# sch-knx-valve-control_v1_0.net
KiCad netlist of a schematic drawn in EasyEDA
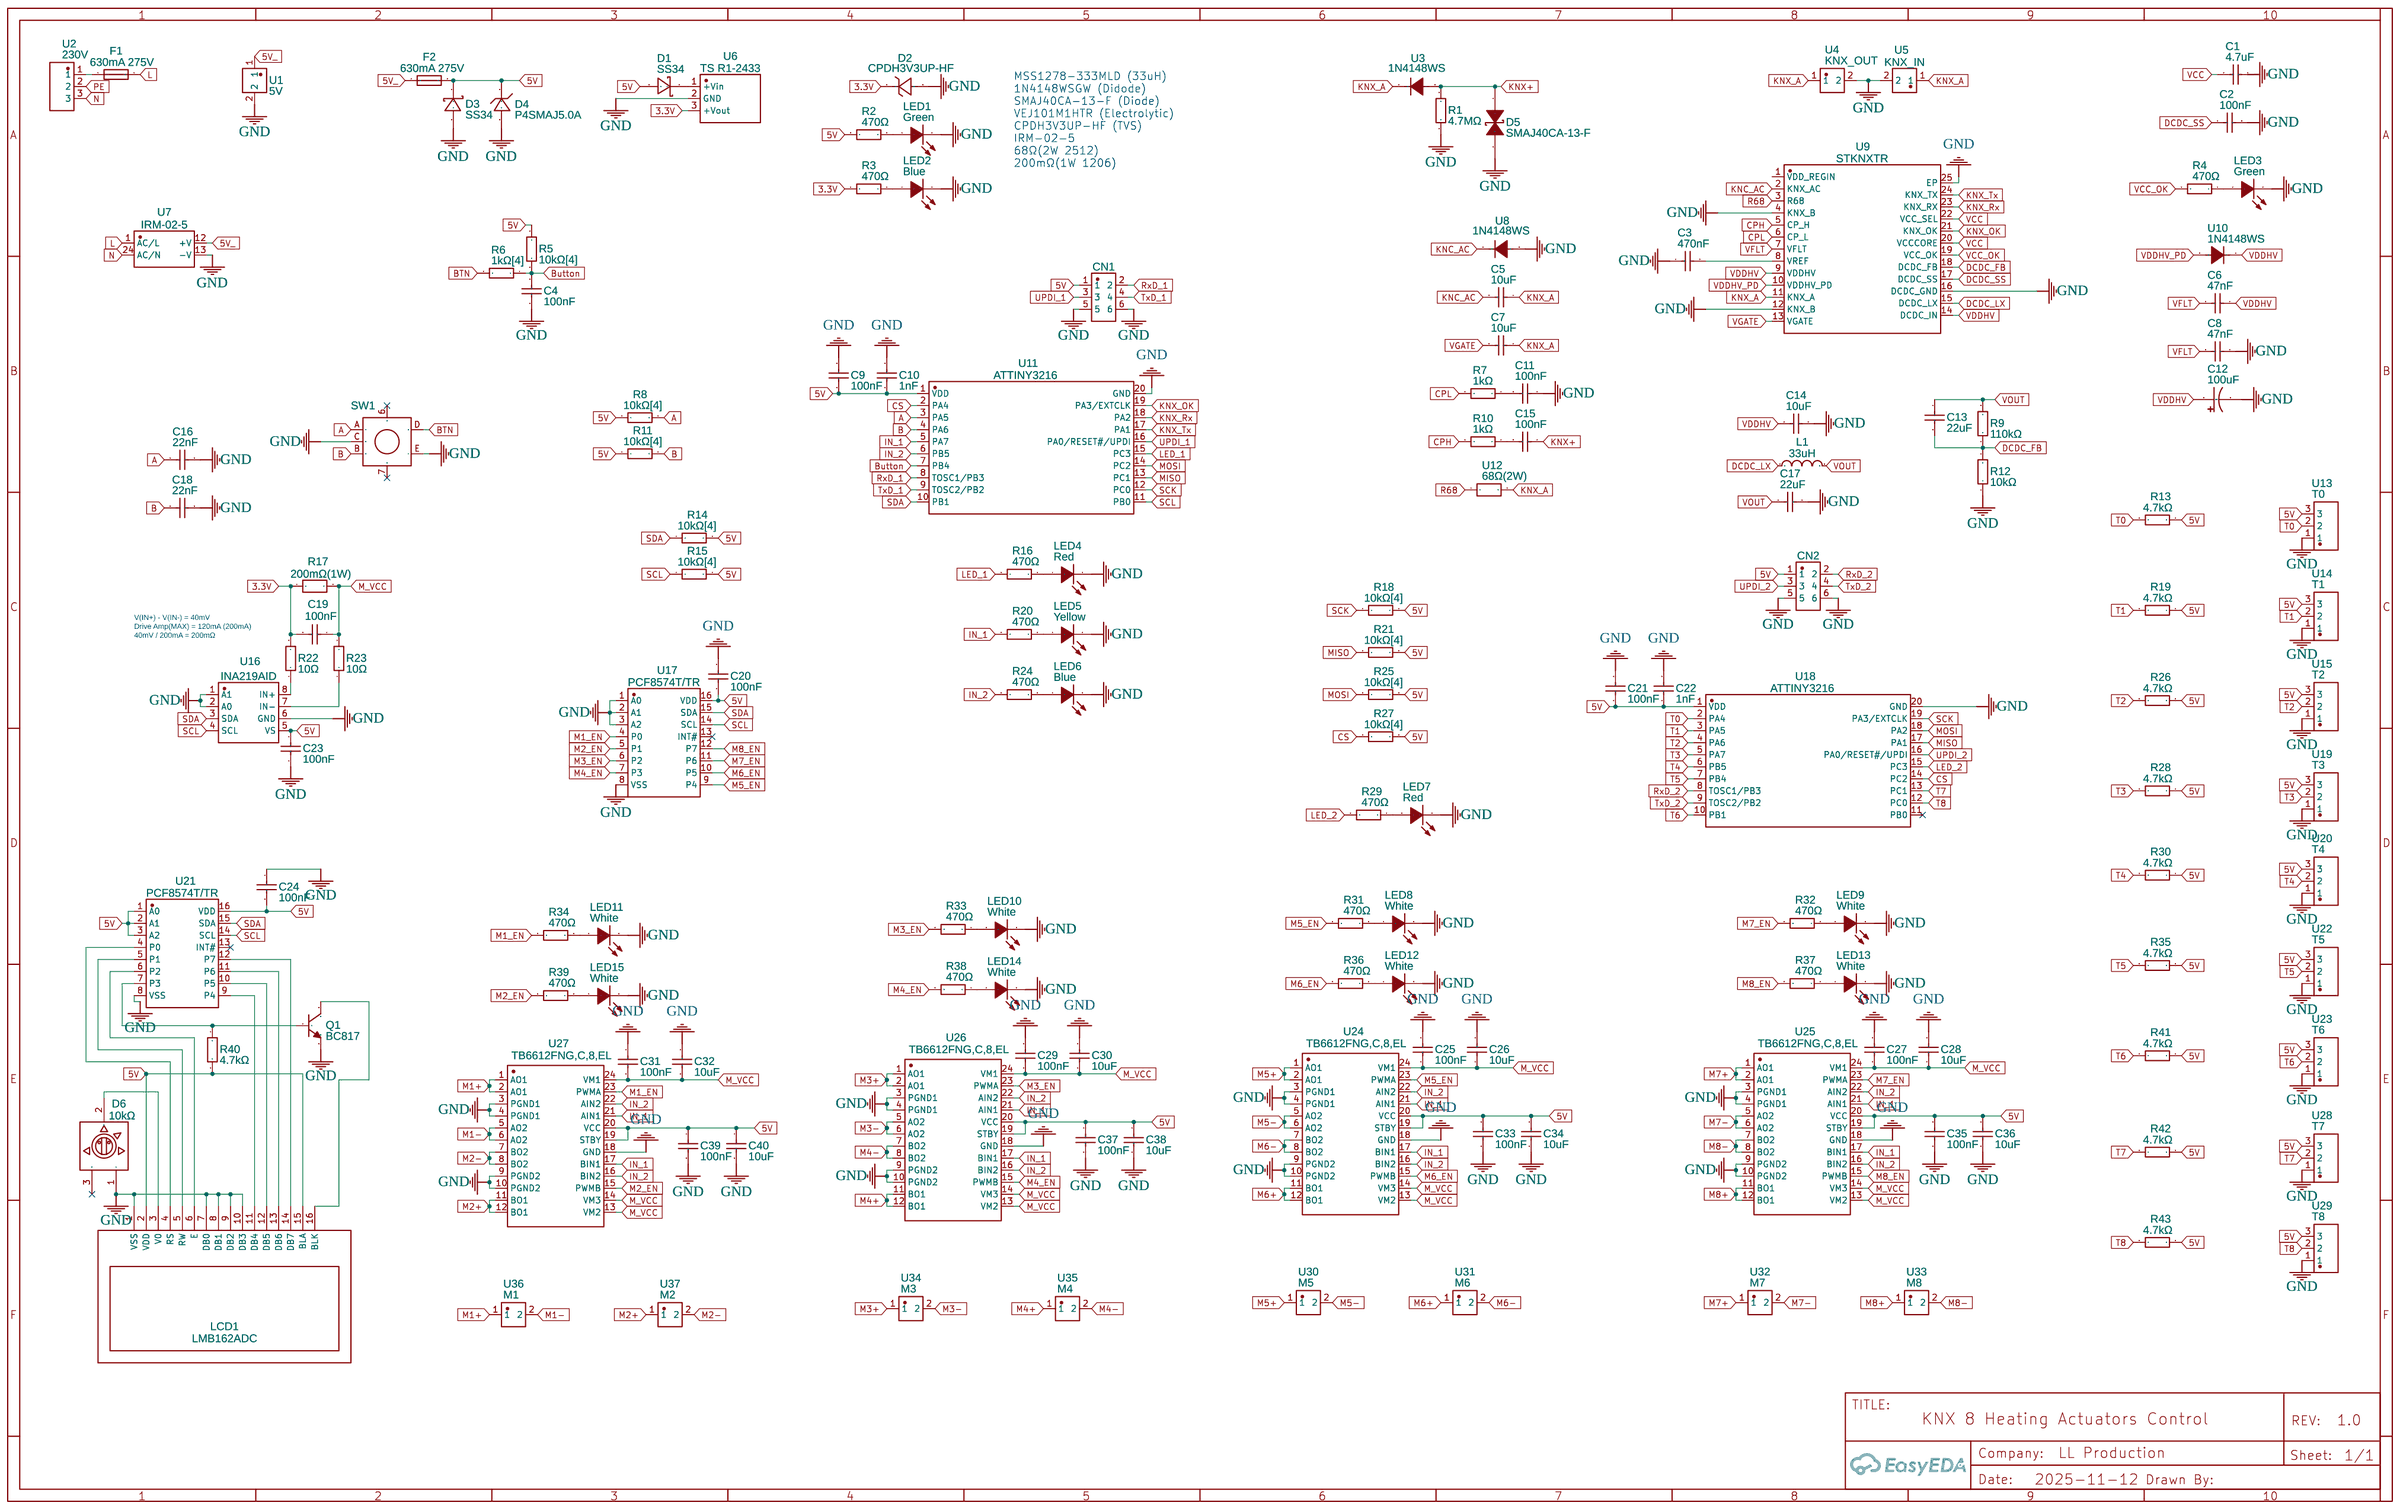
[diagram p0: schematic sheet]

(export (version "E")
  (design (tool "Eeschema 10.0.6"))
  (components
    (comp (ref "C1")
      (value "4.7uF")
      (fields (field (name "Manufacturer Part") "CC0603KRX7R9BB103") (field (name "Manufacturer") "YAGEO"))
      (libsource (lib "") (part "CC0603KRX7R9BB103_2"))
    )
    (comp (ref "C2")
      (value "100nF")
      (fields (field (name "Manufacturer Part") "CC0603KRX7R9BB103") (field (name "Manufacturer") "YAGEO"))
      (libsource (lib "") (part "CC0603KRX7R9BB103"))
    )
    (comp (ref "C3")
      (value "470nF")
      (fields (field (name "Manufacturer Part") "CC0603KRX7R9BB103") (field (name "Manufacturer") "YAGEO"))
      (libsource (lib "") (part "CC0603KRX7R9BB103"))
    )
    (comp (ref "C4")
      (value "100nF")
      (fields (field (name "Manufacturer Part") "CC0603KRX7R9BB103") (field (name "Manufacturer") "YAGEO"))
      (libsource (lib "") (part "CC0603KRX7R9BB103_1"))
    )
    (comp (ref "C5")
      (value "10uF")
      (fields (field (name "Manufacturer Part") "CC0603KRX7R9BB103") (field (name "Manufacturer") "YAGEO"))
      (libsource (lib "") (part "CC0603KRX7R9BB103_2"))
    )
    (comp (ref "C6")
      (value "47nF")
      (fields (field (name "Manufacturer Part") "CC0603KRX7R9BB103") (field (name "Manufacturer") "YAGEO"))
      (libsource (lib "") (part "CC0603KRX7R9BB103_2"))
    )
    (comp (ref "C7")
      (value "10uF")
      (fields (field (name "Manufacturer Part") "CC0603KRX7R9BB103") (field (name "Manufacturer") "YAGEO"))
      (libsource (lib "") (part "CC0603KRX7R9BB103_2"))
    )
    (comp (ref "C8")
      (value "47nF")
      (fields (field (name "Manufacturer Part") "CC0603KRX7R9BB103") (field (name "Manufacturer") "YAGEO"))
      (libsource (lib "") (part "CC0603KRX7R9BB103_2"))
    )
    (comp (ref "C9")
      (value "100nF")
      (fields (field (name "Manufacturer Part") "CC0603KRX7R9BB103") (field (name "Manufacturer") "YAGEO"))
      (libsource (lib "") (part "CC0603KRX7R9BB103_3"))
    )
    (comp (ref "C10")
      (value "1nF")
      (fields (field (name "Manufacturer Part") "CC0603KRX7R9BB103") (field (name "Manufacturer") "YAGEO"))
      (libsource (lib "") (part "CC0603KRX7R9BB103_3"))
    )
    (comp (ref "C11")
      (value "100nF")
      (fields (field (name "Manufacturer Part") "CC0603KRX7R9BB103") (field (name "Manufacturer") "YAGEO"))
      (libsource (lib "") (part "CC0603KRX7R9BB103_2"))
    )
    (comp (ref "C12")
      (value "100uF")
      (fields (field (name "Manufacturer Part") "VEJ101M1HTR-0810") (field (name "Manufacturer") "Lelon(立隆)"))
      (libsource (lib "") (part "VEJ101M1HTR-0810"))
    )
    (comp (ref "C13")
      (value "22uF")
      (fields (field (name "Manufacturer Part") "CC0603KRX7R9BB103") (field (name "Manufacturer") "YAGEO"))
      (libsource (lib "") (part "CC0603KRX7R9BB103_1"))
    )
    (comp (ref "C14")
      (value "10uF")
      (fields (field (name "Manufacturer Part") "CC0603KRX7R9BB103") (field (name "Manufacturer") "YAGEO"))
      (libsource (lib "") (part "CC0603KRX7R9BB103"))
    )
    (comp (ref "C15")
      (value "100nF")
      (fields (field (name "Manufacturer Part") "CC0603KRX7R9BB103") (field (name "Manufacturer") "YAGEO"))
      (libsource (lib "") (part "CC0603KRX7R9BB103_2"))
    )
    (comp (ref "C16")
      (value "22nF")
      (fields (field (name "Manufacturer Part") "CC0603KRX7R9BB103") (field (name "Manufacturer") "YAGEO"))
      (libsource (lib "") (part "CC0603KRX7R9BB103_2"))
    )
    (comp (ref "C17")
      (value "22uF")
      (fields (field (name "Manufacturer Part") "CC0603KRX7R9BB103") (field (name "Manufacturer") "YAGEO"))
      (libsource (lib "") (part "CC0603KRX7R9BB103"))
    )
    (comp (ref "C18")
      (value "22nF")
      (fields (field (name "Manufacturer Part") "CC0603KRX7R9BB103") (field (name "Manufacturer") "YAGEO"))
      (libsource (lib "") (part "CC0603KRX7R9BB103_2"))
    )
    (comp (ref "C19")
      (value "100nF")
      (fields (field (name "Manufacturer Part") "CC0603KRX7R9BB103") (field (name "Manufacturer") "YAGEO"))
      (libsource (lib "") (part "CC0603KRX7R9BB103_2"))
    )
    (comp (ref "C20")
      (value "100nF")
      (fields (field (name "Manufacturer Part") "CC0603KRX7R9BB103") (field (name "Manufacturer") "YAGEO"))
      (libsource (lib "") (part "CC0603KRX7R9BB103_1"))
    )
    (comp (ref "C21")
      (value "100nF")
      (fields (field (name "Manufacturer Part") "CC0603KRX7R9BB103") (field (name "Manufacturer") "YAGEO"))
      (libsource (lib "") (part "CC0603KRX7R9BB103_3"))
    )
    (comp (ref "C22")
      (value "1nF")
      (fields (field (name "Manufacturer Part") "CC0603KRX7R9BB103") (field (name "Manufacturer") "YAGEO"))
      (libsource (lib "") (part "CC0603KRX7R9BB103_3"))
    )
    (comp (ref "C23")
      (value "100nF")
      (fields (field (name "Manufacturer Part") "CC0603KRX7R9BB103") (field (name "Manufacturer") "YAGEO"))
      (libsource (lib "") (part "CC0603KRX7R9BB103_1"))
    )
    (comp (ref "C24")
      (value "100nF")
      (fields (field (name "Manufacturer Part") "CC0603KRX7R9BB103") (field (name "Manufacturer") "YAGEO"))
      (libsource (lib "") (part "CC0603KRX7R9BB103_1"))
    )
    (comp (ref "C25")
      (value "100nF")
      (fields (field (name "Manufacturer Part") "CC0603KRX7R9BB103") (field (name "Manufacturer") "YAGEO"))
      (libsource (lib "") (part "CC0603KRX7R9BB103_1"))
    )
    (comp (ref "C26")
      (value "10uF")
      (fields (field (name "Manufacturer Part") "CC0603KRX7R9BB103") (field (name "Manufacturer") "YAGEO"))
      (libsource (lib "") (part "CC0603KRX7R9BB103_1"))
    )
    (comp (ref "C27")
      (value "100nF")
      (fields (field (name "Manufacturer Part") "CC0603KRX7R9BB103") (field (name "Manufacturer") "YAGEO"))
      (libsource (lib "") (part "CC0603KRX7R9BB103_1"))
    )
    (comp (ref "C28")
      (value "10uF")
      (fields (field (name "Manufacturer Part") "CC0603KRX7R9BB103") (field (name "Manufacturer") "YAGEO"))
      (libsource (lib "") (part "CC0603KRX7R9BB103_1"))
    )
    (comp (ref "C29")
      (value "100nF")
      (fields (field (name "Manufacturer Part") "CC0603KRX7R9BB103") (field (name "Manufacturer") "YAGEO"))
      (libsource (lib "") (part "CC0603KRX7R9BB103_1"))
    )
    (comp (ref "C30")
      (value "10uF")
      (fields (field (name "Manufacturer Part") "CC0603KRX7R9BB103") (field (name "Manufacturer") "YAGEO"))
      (libsource (lib "") (part "CC0603KRX7R9BB103_1"))
    )
    (comp (ref "C31")
      (value "100nF")
      (fields (field (name "Manufacturer Part") "CC0603KRX7R9BB103") (field (name "Manufacturer") "YAGEO"))
      (libsource (lib "") (part "CC0603KRX7R9BB103_1"))
    )
    (comp (ref "C32")
      (value "10uF")
      (fields (field (name "Manufacturer Part") "CC0603KRX7R9BB103") (field (name "Manufacturer") "YAGEO"))
      (libsource (lib "") (part "CC0603KRX7R9BB103_1"))
    )
    (comp (ref "C33")
      (value "100nF")
      (fields (field (name "Manufacturer Part") "CC0603KRX7R9BB103") (field (name "Manufacturer") "YAGEO"))
      (libsource (lib "") (part "CC0603KRX7R9BB103_1"))
    )
    (comp (ref "C34")
      (value "10uF")
      (fields (field (name "Manufacturer Part") "CC0603KRX7R9BB103") (field (name "Manufacturer") "YAGEO"))
      (libsource (lib "") (part "CC0603KRX7R9BB103_1"))
    )
    (comp (ref "C35")
      (value "100nF")
      (fields (field (name "Manufacturer Part") "CC0603KRX7R9BB103") (field (name "Manufacturer") "YAGEO"))
      (libsource (lib "") (part "CC0603KRX7R9BB103_1"))
    )
    (comp (ref "C36")
      (value "10uF")
      (fields (field (name "Manufacturer Part") "CC0603KRX7R9BB103") (field (name "Manufacturer") "YAGEO"))
      (libsource (lib "") (part "CC0603KRX7R9BB103_1"))
    )
    (comp (ref "C37")
      (value "100nF")
      (fields (field (name "Manufacturer Part") "CC0603KRX7R9BB103") (field (name "Manufacturer") "YAGEO"))
      (libsource (lib "") (part "CC0603KRX7R9BB103_1"))
    )
    (comp (ref "C38")
      (value "10uF")
      (fields (field (name "Manufacturer Part") "CC0603KRX7R9BB103") (field (name "Manufacturer") "YAGEO"))
      (libsource (lib "") (part "CC0603KRX7R9BB103_1"))
    )
    (comp (ref "C39")
      (value "100nF")
      (fields (field (name "Manufacturer Part") "CC0603KRX7R9BB103") (field (name "Manufacturer") "YAGEO"))
      (libsource (lib "") (part "CC0603KRX7R9BB103_1"))
    )
    (comp (ref "C40")
      (value "10uF")
      (fields (field (name "Manufacturer Part") "CC0603KRX7R9BB103") (field (name "Manufacturer") "YAGEO"))
      (libsource (lib "") (part "CC0603KRX7R9BB103_1"))
    )
    (comp (ref "CN1")
      (value "321006SG0ABK00A01")
      (fields (field (name "Manufacturer") "JILN(锦凌)"))
      (libsource (lib "") (part "321006SG0ABK00A01"))
    )
    (comp (ref "CN2")
      (value "321006SG0ABK00A01")
      (fields (field (name "Manufacturer") "JILN(锦凌)"))
      (libsource (lib "") (part "321006SG0ABK00A01"))
    )
    (comp (ref "D1")
      (value "SS34")
      (fields (field (name "Manufacturer") "MDD"))
      (libsource (lib "") (part "SS34_C8678_1"))
    )
    (comp (ref "D2")
      (value "CPDH3V3UP-HF")
      (fields (field (name "Manufacturer Part") "SOD-523"))
      (libsource (lib "") (part "SOD-523"))
    )
    (comp (ref "D3")
      (value "SS34")
      (fields (field (name "Manufacturer") "MDD"))
      (libsource (lib "") (part "SS34_C8678"))
    )
    (comp (ref "D4")
      (value "P4SMAJ5.0A")
      (fields
        (field (name "Manufacturer Part") "P4SMAJ12A_R1_00001")
        (field (name "Manufacturer") "PANJIT(强茂)")
      )
      (libsource (lib "") (part "P4SMAJ12A-PEC"))
    )
    (comp (ref "D5")
      (value "SMAJ40CA-13-F")
      (fields (field (name "Manufacturer") "DIODES(美台)"))
      (libsource (lib "") (part "SMAJ40CA-13-F"))
    )
    (comp (ref "D6")
      (value "10kΩ")
      (fields (field (name "Manufacturer Part") "3314G-1-103E") (field (name "Manufacturer") "BOURNS"))
      (libsource (lib "") (part "3314G-1-103E"))
    )
    (comp (ref "F1")
      (value "630mA 275V")
      (fields (field (name "Manufacturer Part") "S1032-F-60.0A") (field (name "Manufacturer") "SART(萨特)"))
      (libsource (lib "") (part "S1032-F-60.0A"))
    )
    (comp (ref "F2")
      (value "630mA 275V")
      (fields (field (name "Manufacturer Part") "S1032-F-60.0A") (field (name "Manufacturer") "SART(萨特)"))
      (libsource (lib "") (part "S1032-F-60.0A"))
    )
    (comp (ref "L1")
      (value "33uH")
      (fields (field (name "Manufacturer Part") "MSS1278-333MLD"))
      (libsource (lib "") (part "MSS1278-333MLD"))
    )
    (comp (ref "LCD1")
      (value "LMB162ADC")
      (fields (field (name "Manufacturer") "TOPWAY"))
      (libsource (lib "") (part "LMB162ADC"))
    )
    (comp (ref "LED1")
      (value "Green")
      (fields (field (name "Manufacturer Part") "SZYY0603R") (field (name "Manufacturer") "yongyu(永裕光电)"))
      (libsource (lib "") (part "SZYY0603R"))
    )
    (comp (ref "LED2")
      (value "Blue")
      (fields (field (name "Manufacturer Part") "SZYY0603R") (field (name "Manufacturer") "yongyu(永裕光电)"))
      (libsource (lib "") (part "SZYY0603R"))
    )
    (comp (ref "LED3")
      (value "Green")
      (fields (field (name "Manufacturer Part") "SZYY0603R") (field (name "Manufacturer") "yongyu(永裕光电)"))
      (libsource (lib "") (part "SZYY0603R"))
    )
    (comp (ref "LED4")
      (value "Red")
      (fields (field (name "Manufacturer Part") "SZYY0603R") (field (name "Manufacturer") "yongyu(永裕光电)"))
      (libsource (lib "") (part "SZYY0603R"))
    )
    (comp (ref "LED5")
      (value "Yellow")
      (fields (field (name "Manufacturer Part") "SZYY0603R") (field (name "Manufacturer") "yongyu(永裕光电)"))
      (libsource (lib "") (part "SZYY0603R"))
    )
    (comp (ref "LED6")
      (value "Blue")
      (fields (field (name "Manufacturer Part") "SZYY0603R") (field (name "Manufacturer") "yongyu(永裕光电)"))
      (libsource (lib "") (part "SZYY0603R"))
    )
    (comp (ref "LED7")
      (value "Red")
      (fields (field (name "Manufacturer Part") "SZYY0603R") (field (name "Manufacturer") "yongyu(永裕光电)"))
      (libsource (lib "") (part "SZYY0603R"))
    )
    (comp (ref "LED8")
      (value "White")
      (fields (field (name "Manufacturer Part") "SZYY0603R") (field (name "Manufacturer") "yongyu(永裕光电)"))
      (libsource (lib "") (part "SZYY0603R"))
    )
    (comp (ref "LED9")
      (value "White")
      (fields (field (name "Manufacturer Part") "SZYY0603R") (field (name "Manufacturer") "yongyu(永裕光电)"))
      (libsource (lib "") (part "SZYY0603R"))
    )
    (comp (ref "LED10")
      (value "White")
      (fields (field (name "Manufacturer Part") "SZYY0603R") (field (name "Manufacturer") "yongyu(永裕光电)"))
      (libsource (lib "") (part "SZYY0603R"))
    )
    (comp (ref "LED11")
      (value "White")
      (fields (field (name "Manufacturer Part") "SZYY0603R") (field (name "Manufacturer") "yongyu(永裕光电)"))
      (libsource (lib "") (part "SZYY0603R"))
    )
    (comp (ref "LED12")
      (value "White")
      (fields (field (name "Manufacturer Part") "SZYY0603R") (field (name "Manufacturer") "yongyu(永裕光电)"))
      (libsource (lib "") (part "SZYY0603R"))
    )
    (comp (ref "LED13")
      (value "White")
      (fields (field (name "Manufacturer Part") "SZYY0603R") (field (name "Manufacturer") "yongyu(永裕光电)"))
      (libsource (lib "") (part "SZYY0603R"))
    )
    (comp (ref "LED14")
      (value "White")
      (fields (field (name "Manufacturer Part") "SZYY0603R") (field (name "Manufacturer") "yongyu(永裕光电)"))
      (libsource (lib "") (part "SZYY0603R"))
    )
    (comp (ref "LED15")
      (value "White")
      (fields (field (name "Manufacturer Part") "SZYY0603R") (field (name "Manufacturer") "yongyu(永裕光电)"))
      (libsource (lib "") (part "SZYY0603R"))
    )
    (comp (ref "Q1")
      (value "BC817")
      (fields (field (name "Manufacturer Part") "BC817-40,215") (field (name "Manufacturer") "Nexperia(安世)"))
      (libsource (lib "") (part "BC817-40,215"))
    )
    (comp (ref "R1")
      (value "4.7MΩ")
      (fields (field (name "Manufacturer Part") "CR0603FA1001G") (field (name "Manufacturer") "LIZ(丽智电子)"))
      (libsource (lib "") (part "CR0603FA1001G_C126900_1"))
    )
    (comp (ref "R2")
      (value "470Ω")
      (fields (field (name "Manufacturer Part") "CR0603FA1001G") (field (name "Manufacturer") "LIZ(丽智电子)"))
      (libsource (lib "") (part "CR0603FA1001G_C126900"))
    )
    (comp (ref "R3")
      (value "470Ω")
      (fields (field (name "Manufacturer Part") "CR0603FA1001G") (field (name "Manufacturer") "LIZ(丽智电子)"))
      (libsource (lib "") (part "CR0603FA1001G_C126900"))
    )
    (comp (ref "R4")
      (value "470Ω")
      (fields (field (name "Manufacturer Part") "CR0603FA1001G") (field (name "Manufacturer") "LIZ(丽智电子)"))
      (libsource (lib "") (part "CR0603FA1001G_C126900"))
    )
    (comp (ref "R5")
      (value "10kΩ[4]")
      (fields
        (field (name "Manufacturer Part") "0402WGF1002TCE")
        (field (name "Manufacturer") "UNI-ROYAL(厚声)")
      )
      (libsource (lib "") (part "0402WGF1002TCE_2"))
    )
    (comp (ref "R6")
      (value "1kΩ[4]")
      (fields
        (field (name "Manufacturer Part") "0402WGF1002TCE")
        (field (name "Manufacturer") "UNI-ROYAL(厚声)")
      )
      (libsource (lib "") (part "0402WGF1002TCE"))
    )
    (comp (ref "R7")
      (value "1kΩ")
      (fields (field (name "Manufacturer Part") "CR0603FA1001G") (field (name "Manufacturer") "LIZ(丽智电子)"))
      (libsource (lib "") (part "CR0603FA1001G_C126900"))
    )
    (comp (ref "R8")
      (value "10kΩ[4]")
      (fields
        (field (name "Manufacturer Part") "0402WGF1002TCE")
        (field (name "Manufacturer") "UNI-ROYAL(厚声)")
      )
      (libsource (lib "") (part "0402WGF1002TCE_1"))
    )
    (comp (ref "R9")
      (value "110kΩ")
      (fields (field (name "Manufacturer Part") "CR0603FA1001G") (field (name "Manufacturer") "LIZ(丽智电子)"))
      (libsource (lib "") (part "CR0603FA1001G_C126900_1"))
    )
    (comp (ref "R10")
      (value "1kΩ")
      (fields (field (name "Manufacturer Part") "CR0603FA1001G") (field (name "Manufacturer") "LIZ(丽智电子)"))
      (libsource (lib "") (part "CR0603FA1001G_C126900"))
    )
    (comp (ref "R11")
      (value "10kΩ[4]")
      (fields
        (field (name "Manufacturer Part") "0402WGF1002TCE")
        (field (name "Manufacturer") "UNI-ROYAL(厚声)")
      )
      (libsource (lib "") (part "0402WGF1002TCE_1"))
    )
    (comp (ref "R12")
      (value "10kΩ")
      (fields (field (name "Manufacturer Part") "CR0603FA1001G") (field (name "Manufacturer") "LIZ(丽智电子)"))
      (libsource (lib "") (part "CR0603FA1001G_C126900_1"))
    )
    (comp (ref "R13")
      (value "4.7kΩ")
      (fields (field (name "Manufacturer Part") "CR0603FA1001G") (field (name "Manufacturer") "LIZ(丽智电子)"))
      (libsource (lib "") (part "CR0603FA1001G_C126900"))
    )
    (comp (ref "R14")
      (value "10kΩ[4]")
      (fields
        (field (name "Manufacturer Part") "0402WGF1002TCE")
        (field (name "Manufacturer") "UNI-ROYAL(厚声)")
      )
      (libsource (lib "") (part "0402WGF1002TCE_1"))
    )
    (comp (ref "R15")
      (value "10kΩ[4]")
      (fields
        (field (name "Manufacturer Part") "0402WGF1002TCE")
        (field (name "Manufacturer") "UNI-ROYAL(厚声)")
      )
      (libsource (lib "") (part "0402WGF1002TCE_1"))
    )
    (comp (ref "R16")
      (value "470Ω")
      (fields (field (name "Manufacturer Part") "CR0603FA1001G") (field (name "Manufacturer") "LIZ(丽智电子)"))
      (libsource (lib "") (part "CR0603FA1001G_C126900"))
    )
    (comp (ref "R17")
      (value "200mΩ(1W)")
      (fields (field (name "Manufacturer Part") "SCR1206F1M1") (field (name "Manufacturer") "VO(翔胜)"))
      (libsource (lib "") (part "SCR1206F1M1"))
    )
    (comp (ref "R18")
      (value "10kΩ[4]")
      (fields
        (field (name "Manufacturer Part") "0402WGF1002TCE")
        (field (name "Manufacturer") "UNI-ROYAL(厚声)")
      )
      (libsource (lib "") (part "0402WGF1002TCE_1"))
    )
    (comp (ref "R19")
      (value "4.7kΩ")
      (fields (field (name "Manufacturer Part") "CR0603FA1001G") (field (name "Manufacturer") "LIZ(丽智电子)"))
      (libsource (lib "") (part "CR0603FA1001G_C126900"))
    )
    (comp (ref "R20")
      (value "470Ω")
      (fields (field (name "Manufacturer Part") "CR0603FA1001G") (field (name "Manufacturer") "LIZ(丽智电子)"))
      (libsource (lib "") (part "CR0603FA1001G_C126900"))
    )
    (comp (ref "R21")
      (value "10kΩ[4]")
      (fields
        (field (name "Manufacturer Part") "0402WGF1002TCE")
        (field (name "Manufacturer") "UNI-ROYAL(厚声)")
      )
      (libsource (lib "") (part "0402WGF1002TCE_1"))
    )
    (comp (ref "R22")
      (value "10Ω")
      (fields (field (name "Manufacturer Part") "CR0603FA1001G") (field (name "Manufacturer") "LIZ(丽智电子)"))
      (libsource (lib "") (part "CR0603FA1001G_C126900_1"))
    )
    (comp (ref "R23")
      (value "10Ω")
      (fields (field (name "Manufacturer Part") "CR0603FA1001G") (field (name "Manufacturer") "LIZ(丽智电子)"))
      (libsource (lib "") (part "CR0603FA1001G_C126900_1"))
    )
    (comp (ref "R24")
      (value "470Ω")
      (fields (field (name "Manufacturer Part") "CR0603FA1001G") (field (name "Manufacturer") "LIZ(丽智电子)"))
      (libsource (lib "") (part "CR0603FA1001G_C126900"))
    )
    (comp (ref "R25")
      (value "10kΩ[4]")
      (fields
        (field (name "Manufacturer Part") "0402WGF1002TCE")
        (field (name "Manufacturer") "UNI-ROYAL(厚声)")
      )
      (libsource (lib "") (part "0402WGF1002TCE_1"))
    )
    (comp (ref "R26")
      (value "4.7kΩ")
      (fields (field (name "Manufacturer Part") "CR0603FA1001G") (field (name "Manufacturer") "LIZ(丽智电子)"))
      (libsource (lib "") (part "CR0603FA1001G_C126900"))
    )
    (comp (ref "R27")
      (value "10kΩ[4]")
      (fields
        (field (name "Manufacturer Part") "0402WGF1002TCE")
        (field (name "Manufacturer") "UNI-ROYAL(厚声)")
      )
      (libsource (lib "") (part "0402WGF1002TCE_1"))
    )
    (comp (ref "R28")
      (value "4.7kΩ")
      (fields (field (name "Manufacturer Part") "CR0603FA1001G") (field (name "Manufacturer") "LIZ(丽智电子)"))
      (libsource (lib "") (part "CR0603FA1001G_C126900"))
    )
    (comp (ref "R29")
      (value "470Ω")
      (fields (field (name "Manufacturer Part") "CR0603FA1001G") (field (name "Manufacturer") "LIZ(丽智电子)"))
      (libsource (lib "") (part "CR0603FA1001G_C126900"))
    )
    (comp (ref "R30")
      (value "4.7kΩ")
      (fields (field (name "Manufacturer Part") "CR0603FA1001G") (field (name "Manufacturer") "LIZ(丽智电子)"))
      (libsource (lib "") (part "CR0603FA1001G_C126900"))
    )
    (comp (ref "R31")
      (value "470Ω")
      (fields (field (name "Manufacturer Part") "CR0603FA1001G") (field (name "Manufacturer") "LIZ(丽智电子)"))
      (libsource (lib "") (part "CR0603FA1001G_C126900"))
    )
    (comp (ref "R32")
      (value "470Ω")
      (fields (field (name "Manufacturer Part") "CR0603FA1001G") (field (name "Manufacturer") "LIZ(丽智电子)"))
      (libsource (lib "") (part "CR0603FA1001G_C126900"))
    )
    (comp (ref "R33")
      (value "470Ω")
      (fields (field (name "Manufacturer Part") "CR0603FA1001G") (field (name "Manufacturer") "LIZ(丽智电子)"))
      (libsource (lib "") (part "CR0603FA1001G_C126900"))
    )
    (comp (ref "R34")
      (value "470Ω")
      (fields (field (name "Manufacturer Part") "CR0603FA1001G") (field (name "Manufacturer") "LIZ(丽智电子)"))
      (libsource (lib "") (part "CR0603FA1001G_C126900"))
    )
    (comp (ref "R35")
      (value "4.7kΩ")
      (fields (field (name "Manufacturer Part") "CR0603FA1001G") (field (name "Manufacturer") "LIZ(丽智电子)"))
      (libsource (lib "") (part "CR0603FA1001G_C126900"))
    )
    (comp (ref "R36")
      (value "470Ω")
      (fields (field (name "Manufacturer Part") "CR0603FA1001G") (field (name "Manufacturer") "LIZ(丽智电子)"))
      (libsource (lib "") (part "CR0603FA1001G_C126900"))
    )
    (comp (ref "R37")
      (value "470Ω")
      (fields (field (name "Manufacturer Part") "CR0603FA1001G") (field (name "Manufacturer") "LIZ(丽智电子)"))
      (libsource (lib "") (part "CR0603FA1001G_C126900"))
    )
    (comp (ref "R38")
      (value "470Ω")
      (fields (field (name "Manufacturer Part") "CR0603FA1001G") (field (name "Manufacturer") "LIZ(丽智电子)"))
      (libsource (lib "") (part "CR0603FA1001G_C126900"))
    )
    (comp (ref "R39")
      (value "470Ω")
      (fields (field (name "Manufacturer Part") "CR0603FA1001G") (field (name "Manufacturer") "LIZ(丽智电子)"))
      (libsource (lib "") (part "CR0603FA1001G_C126900"))
    )
    (comp (ref "R40")
      (value "4.7kΩ")
      (fields (field (name "Manufacturer Part") "CR0603FA1001G") (field (name "Manufacturer") "LIZ(丽智电子)"))
      (libsource (lib "") (part "CR0603FA1001G_C126900_2"))
    )
    (comp (ref "R41")
      (value "4.7kΩ")
      (fields (field (name "Manufacturer Part") "CR0603FA1001G") (field (name "Manufacturer") "LIZ(丽智电子)"))
      (libsource (lib "") (part "CR0603FA1001G_C126900"))
    )
    (comp (ref "R42")
      (value "4.7kΩ")
      (fields (field (name "Manufacturer Part") "CR0603FA1001G") (field (name "Manufacturer") "LIZ(丽智电子)"))
      (libsource (lib "") (part "CR0603FA1001G_C126900"))
    )
    (comp (ref "R43")
      (value "4.7kΩ")
      (fields (field (name "Manufacturer Part") "CR0603FA1001G") (field (name "Manufacturer") "LIZ(丽智电子)"))
      (libsource (lib "") (part "CR0603FA1001G_C126900"))
    )
    (comp (ref "SW1")
      (value "EC11L1525G01")
      (fields (field (name "Manufacturer") "ALPSALPINE(阿尔卑斯阿尔派)"))
      (libsource (lib "") (part "EC11L1525G01"))
    )
    (comp (ref "U1")
      (value "5V")
      (fields (field (name "Manufacturer Part") "2P,间距5.08mm,弹片压线升降式"))
      (libsource (lib "") (part "2P,间距5.08MM,弹片压线升降式_1"))
    )
    (comp (ref "U2")
      (value "230V")
      (fields
        (field (name "Manufacturer Part") "DB127V-5.08-3P-GN-S")
        (field (name "Manufacturer") "DIBO(地博电气)")
      )
      (libsource (lib "") (part "DB127V-5.08-3P-GN-S_1"))
    )
    (comp (ref "U3")
      (value "1N4148WS")
      (fields (field (name "Manufacturer") "Zhengxin(正芯)"))
      (libsource (lib "") (part "1N4148WS_1"))
    )
    (comp (ref "U4")
      (value "KNX_OUT")
      (fields (field (name "Manufacturer Part") "2P,间距5.08mm,弹片压线升降式"))
      (libsource (lib "") (part "2P,间距5.08MM,弹片压线升降式"))
    )
    (comp (ref "U5")
      (value "KNX_IN")
      (fields (field (name "Manufacturer Part") "2P,间距5.08mm,弹片压线升降式"))
      (libsource (lib "") (part "2P,间距5.08MM,弹片压线升降式_2"))
    )
    (comp (ref "U6")
      (value "TS R1-2433")
      (fields (field (name "Manufacturer") "TRACO POWER"))
      (libsource (lib "") (part "TS R1-2433"))
    )
    (comp (ref "U7")
      (value "IRM-02-5")
      (fields (field (name "Manufacturer") "MW(明纬)"))
      (libsource (lib "") (part "IRM-02-5"))
    )
    (comp (ref "U8")
      (value "1N4148WS")
      (fields (field (name "Manufacturer") "Zhengxin(正芯)"))
      (libsource (lib "") (part "1N4148WS_1"))
    )
    (comp (ref "U9")
      (value "STKNXTR")
      (fields (field (name "Manufacturer") "ST(意法半导体)"))
      (libsource (lib "") (part "STKNXTR"))
    )
    (comp (ref "U10")
      (value "1N4148WS")
      (fields (field (name "Manufacturer") "Zhengxin(正芯)"))
      (libsource (lib "") (part "1N4148WS"))
    )
    (comp (ref "U11")
      (value "ATTINY3216")
      (fields
        (field (name "Manufacturer Part") "ATTINY1616-SN")
        (field (name "Manufacturer") "MICROCHIP(美国微芯)")
      )
      (libsource (lib "") (part "ATTINY1616-SN_C614136"))
    )
    (comp (ref "U12")
      (value "68Ω(2W)")
      (fields
        (field (name "Manufacturer Part") "HoJLR2512-3W-3.5mR-1%")
        (field (name "Manufacturer") "Milliohm(毫欧)")
      )
      (libsource (lib "") (part "HOJLR2512-3W-3.5MR-1%"))
    )
    (comp (ref "U13")
      (value "T0")
      (fields
        (field (name "Manufacturer Part") "DB127V-5.08-3P-GN-S")
        (field (name "Manufacturer") "DIBO(地博电气)")
      )
      (libsource (lib "") (part "DB127V-5.08-3P-GN-S"))
    )
    (comp (ref "U14")
      (value "T1")
      (fields
        (field (name "Manufacturer Part") "DB127V-5.08-3P-GN-S")
        (field (name "Manufacturer") "DIBO(地博电气)")
      )
      (libsource (lib "") (part "DB127V-5.08-3P-GN-S"))
    )
    (comp (ref "U15")
      (value "T2")
      (fields
        (field (name "Manufacturer Part") "DB127V-5.08-3P-GN-S")
        (field (name "Manufacturer") "DIBO(地博电气)")
      )
      (libsource (lib "") (part "DB127V-5.08-3P-GN-S"))
    )
    (comp (ref "U16")
      (value "INA219AID")
      (fields (field (name "Manufacturer") "TI(德州仪器)"))
      (libsource (lib "") (part "INA219AID"))
    )
    (comp (ref "U17")
      (value "PCF8574T/TR")
      (fields (field (name "Manufacturer") "HGSEMI(华冠)"))
      (libsource (lib "") (part "PCF8574T/TR"))
    )
    (comp (ref "U18")
      (value "ATTINY3216")
      (fields
        (field (name "Manufacturer Part") "ATTINY1616-SN")
        (field (name "Manufacturer") "MICROCHIP(美国微芯)")
      )
      (libsource (lib "") (part "ATTINY1616-SN_C614136"))
    )
    (comp (ref "U19")
      (value "T3")
      (fields
        (field (name "Manufacturer Part") "DB127V-5.08-3P-GN-S")
        (field (name "Manufacturer") "DIBO(地博电气)")
      )
      (libsource (lib "") (part "DB127V-5.08-3P-GN-S"))
    )
    (comp (ref "U20")
      (value "T4")
      (fields
        (field (name "Manufacturer Part") "DB127V-5.08-3P-GN-S")
        (field (name "Manufacturer") "DIBO(地博电气)")
      )
      (libsource (lib "") (part "DB127V-5.08-3P-GN-S"))
    )
    (comp (ref "U21")
      (value "PCF8574T/TR")
      (fields (field (name "Manufacturer") "HGSEMI(华冠)"))
      (libsource (lib "") (part "PCF8574T/TR"))
    )
    (comp (ref "U22")
      (value "T5")
      (fields
        (field (name "Manufacturer Part") "DB127V-5.08-3P-GN-S")
        (field (name "Manufacturer") "DIBO(地博电气)")
      )
      (libsource (lib "") (part "DB127V-5.08-3P-GN-S"))
    )
    (comp (ref "U23")
      (value "T6")
      (fields
        (field (name "Manufacturer Part") "DB127V-5.08-3P-GN-S")
        (field (name "Manufacturer") "DIBO(地博电气)")
      )
      (libsource (lib "") (part "DB127V-5.08-3P-GN-S"))
    )
    (comp (ref "U24")
      (value "TB6612FNG,C,8,EL")
      (fields (field (name "Manufacturer") "TOSHIBA(东芝)"))
      (libsource (lib "") (part "TB6612FNG,C,8,EL"))
    )
    (comp (ref "U25")
      (value "TB6612FNG,C,8,EL")
      (fields (field (name "Manufacturer") "TOSHIBA(东芝)"))
      (libsource (lib "") (part "TB6612FNG,C,8,EL"))
    )
    (comp (ref "U26")
      (value "TB6612FNG,C,8,EL")
      (fields (field (name "Manufacturer") "TOSHIBA(东芝)"))
      (libsource (lib "") (part "TB6612FNG,C,8,EL"))
    )
    (comp (ref "U27")
      (value "TB6612FNG,C,8,EL")
      (fields (field (name "Manufacturer") "TOSHIBA(东芝)"))
      (libsource (lib "") (part "TB6612FNG,C,8,EL"))
    )
    (comp (ref "U28")
      (value "T7")
      (fields
        (field (name "Manufacturer Part") "DB127V-5.08-3P-GN-S")
        (field (name "Manufacturer") "DIBO(地博电气)")
      )
      (libsource (lib "") (part "DB127V-5.08-3P-GN-S"))
    )
    (comp (ref "U29")
      (value "T8")
      (fields
        (field (name "Manufacturer Part") "DB127V-5.08-3P-GN-S")
        (field (name "Manufacturer") "DIBO(地博电气)")
      )
      (libsource (lib "") (part "DB127V-5.08-3P-GN-S"))
    )
    (comp (ref "U30")
      (value "M5")
      (fields (field (name "Manufacturer Part") "2P,间距5.08mm,弹片压线升降式"))
      (libsource (lib "") (part "2P,间距5.08MM,弹片压线升降式"))
    )
    (comp (ref "U31")
      (value "M6")
      (fields (field (name "Manufacturer Part") "2P,间距5.08mm,弹片压线升降式"))
      (libsource (lib "") (part "2P,间距5.08MM,弹片压线升降式"))
    )
    (comp (ref "U32")
      (value "M7")
      (fields (field (name "Manufacturer Part") "2P,间距5.08mm,弹片压线升降式"))
      (libsource (lib "") (part "2P,间距5.08MM,弹片压线升降式"))
    )
    (comp (ref "U33")
      (value "M8")
      (fields (field (name "Manufacturer Part") "2P,间距5.08mm,弹片压线升降式"))
      (libsource (lib "") (part "2P,间距5.08MM,弹片压线升降式"))
    )
    (comp (ref "U34")
      (value "M3")
      (fields (field (name "Manufacturer Part") "2P,间距5.08mm,弹片压线升降式"))
      (libsource (lib "") (part "2P,间距5.08MM,弹片压线升降式"))
    )
    (comp (ref "U35")
      (value "M4")
      (fields (field (name "Manufacturer Part") "2P,间距5.08mm,弹片压线升降式"))
      (libsource (lib "") (part "2P,间距5.08MM,弹片压线升降式"))
    )
    (comp (ref "U36")
      (value "M1")
      (fields (field (name "Manufacturer Part") "2P,间距5.08mm,弹片压线升降式"))
      (libsource (lib "") (part "2P,间距5.08MM,弹片压线升降式"))
    )
    (comp (ref "U37")
      (value "M2")
      (fields (field (name "Manufacturer Part") "2P,间距5.08mm,弹片压线升降式"))
      (libsource (lib "") (part "2P,间距5.08MM,弹片压线升降式"))
    )
  )
  (nets
    (net (code "1") (name "3.3V") (class "Default")
      (node (ref "C19") (pin "2") (pinfunction "2_2") (pintype "input"))
      (node (ref "D2") (pin "1") (pinfunction "K_1") (pintype "unspecified"))
      (node (ref "R17") (pin "1") (pinfunction "1_1") (pintype "unspecified"))
      (node (ref "R22") (pin "2") (pinfunction "2_2") (pintype "input"))
      (node (ref "R3") (pin "2") (pinfunction "2_2") (pintype "input"))
      (node (ref "U6") (pin "3") (pinfunction "+Vout_3") (pintype "unspecified"))
    )
    (net (code "2") (name "5V") (class "Default")
      (node (ref "C10") (pin "1") (pinfunction "1_1") (pintype "input"))
      (node (ref "C20") (pin "2") (pinfunction "2_2") (pintype "input"))
      (node (ref "C21") (pin "1") (pinfunction "1_1") (pintype "input"))
      (node (ref "C22") (pin "1") (pinfunction "1_1") (pintype "input"))
      (node (ref "C23") (pin "1") (pinfunction "1_1") (pintype "input"))
      (node (ref "C24") (pin "2") (pinfunction "2_2") (pintype "input"))
      (node (ref "C33") (pin "1") (pinfunction "1_1") (pintype "input"))
      (node (ref "C34") (pin "1") (pinfunction "1_1") (pintype "input"))
      (node (ref "C35") (pin "1") (pinfunction "1_1") (pintype "input"))
      (node (ref "C36") (pin "1") (pinfunction "1_1") (pintype "input"))
      (node (ref "C37") (pin "1") (pinfunction "1_1") (pintype "input"))
      (node (ref "C38") (pin "1") (pinfunction "1_1") (pintype "input"))
      (node (ref "C39") (pin "1") (pinfunction "1_1") (pintype "input"))
      (node (ref "C40") (pin "1") (pinfunction "1_1") (pintype "input"))
      (node (ref "C9") (pin "1") (pinfunction "1_1") (pintype "input"))
      (node (ref "CN1") (pin "1") (pinfunction "1_1") (pintype "unspecified"))
      (node (ref "CN2") (pin "1") (pinfunction "1_1") (pintype "unspecified"))
      (node (ref "D1") (pin "2") (pinfunction "A_2") (pintype "unspecified"))
      (node (ref "D3") (pin "1") (pinfunction "K_1") (pintype "unspecified"))
      (node (ref "D4") (pin "1") (pinfunction "C_1") (pintype "unspecified"))
      (node (ref "F2") (pin "2") (pinfunction "2_2") (pintype "unspecified"))
      (node (ref "LCD1") (pin "15") (pinfunction "BLA_15") (pintype "unspecified"))
      (node (ref "LCD1") (pin "2") (pinfunction "VDD_2") (pintype "unspecified"))
      (node (ref "R11") (pin "1") (pinfunction "1_1") (pintype "input"))
      (node (ref "R13") (pin "1") (pinfunction "1_1") (pintype "input"))
      (node (ref "R14") (pin "2") (pinfunction "2_2") (pintype "input"))
      (node (ref "R15") (pin "2") (pinfunction "2_2") (pintype "input"))
      (node (ref "R18") (pin "2") (pinfunction "2_2") (pintype "input"))
      (node (ref "R19") (pin "1") (pinfunction "1_1") (pintype "input"))
      (node (ref "R2") (pin "2") (pinfunction "2_2") (pintype "input"))
      (node (ref "R21") (pin "2") (pinfunction "2_2") (pintype "input"))
      (node (ref "R25") (pin "2") (pinfunction "2_2") (pintype "input"))
      (node (ref "R26") (pin "1") (pinfunction "1_1") (pintype "input"))
      (node (ref "R27") (pin "2") (pinfunction "2_2") (pintype "input"))
      (node (ref "R28") (pin "1") (pinfunction "1_1") (pintype "input"))
      (node (ref "R30") (pin "1") (pinfunction "1_1") (pintype "input"))
      (node (ref "R35") (pin "1") (pinfunction "1_1") (pintype "input"))
      (node (ref "R40") (pin "2") (pinfunction "2_2") (pintype "input"))
      (node (ref "R41") (pin "1") (pinfunction "1_1") (pintype "input"))
      (node (ref "R42") (pin "1") (pinfunction "1_1") (pintype "input"))
      (node (ref "R43") (pin "1") (pinfunction "1_1") (pintype "input"))
      (node (ref "R5") (pin "1") (pinfunction "1_1") (pintype "input"))
      (node (ref "R8") (pin "1") (pinfunction "1_1") (pintype "input"))
      (node (ref "U11") (pin "1") (pinfunction "VDD_1") (pintype "unspecified"))
      (node (ref "U13") (pin "3") (pinfunction "3_3") (pintype "unspecified"))
      (node (ref "U14") (pin "3") (pinfunction "3_3") (pintype "unspecified"))
      (node (ref "U15") (pin "3") (pinfunction "3_3") (pintype "unspecified"))
      (node (ref "U16") (pin "5") (pinfunction "VS_5") (pintype "unspecified"))
      (node (ref "U17") (pin "16") (pinfunction "VDD_16") (pintype "unspecified"))
      (node (ref "U18") (pin "1") (pinfunction "VDD_1") (pintype "unspecified"))
      (node (ref "U19") (pin "3") (pinfunction "3_3") (pintype "unspecified"))
      (node (ref "U20") (pin "3") (pinfunction "3_3") (pintype "unspecified"))
      (node (ref "U21") (pin "1") (pinfunction "A0_1") (pintype "unspecified"))
      (node (ref "U21") (pin "16") (pinfunction "VDD_16") (pintype "unspecified"))
      (node (ref "U21") (pin "2") (pinfunction "A1_2") (pintype "unspecified"))
      (node (ref "U21") (pin "3") (pinfunction "A2_3") (pintype "unspecified"))
      (node (ref "U22") (pin "3") (pinfunction "3_3") (pintype "unspecified"))
      (node (ref "U23") (pin "3") (pinfunction "3_3") (pintype "unspecified"))
      (node (ref "U24") (pin "19") (pinfunction "STBY_19") (pintype "unspecified"))
      (node (ref "U24") (pin "20") (pinfunction "VCC_20") (pintype "unspecified"))
      (node (ref "U25") (pin "19") (pinfunction "STBY_19") (pintype "unspecified"))
      (node (ref "U25") (pin "20") (pinfunction "VCC_20") (pintype "unspecified"))
      (node (ref "U26") (pin "19") (pinfunction "STBY_19") (pintype "unspecified"))
      (node (ref "U26") (pin "20") (pinfunction "VCC_20") (pintype "unspecified"))
      (node (ref "U27") (pin "19") (pinfunction "STBY_19") (pintype "unspecified"))
      (node (ref "U27") (pin "20") (pinfunction "VCC_20") (pintype "unspecified"))
      (node (ref "U28") (pin "3") (pinfunction "3_3") (pintype "unspecified"))
      (node (ref "U29") (pin "3") (pinfunction "3_3") (pintype "unspecified"))
    )
    (net (code "3") (name "5V_") (class "Default")
      (node (ref "F2") (pin "1") (pinfunction "1_1") (pintype "unspecified"))
      (node (ref "U1") (pin "1") (pinfunction "1_1") (pintype "unspecified"))
      (node (ref "U7") (pin "12") (pinfunction "+V_12") (pintype "unspecified"))
    )
    (net (code "4") (name "A") (class "Default")
      (node (ref "C16") (pin "2") (pinfunction "2_2") (pintype "input"))
      (node (ref "R8") (pin "2") (pinfunction "2_2") (pintype "input"))
      (node (ref "SW1") (pin "A") (pinfunction "A_A") (pintype "unspecified"))
      (node (ref "U11") (pin "3") (pinfunction "PA5_3") (pintype "unspecified"))
    )
    (net (code "5") (name "B") (class "Default")
      (node (ref "C18") (pin "2") (pinfunction "2_2") (pintype "input"))
      (node (ref "R11") (pin "2") (pinfunction "2_2") (pintype "input"))
      (node (ref "SW1") (pin "B") (pinfunction "B_B") (pintype "unspecified"))
      (node (ref "U11") (pin "4") (pinfunction "PA6_4") (pintype "unspecified"))
    )
    (net (code "6") (name "BTN") (class "Default")
      (node (ref "R6") (pin "2") (pinfunction "2_2") (pintype "input"))
      (node (ref "SW1") (pin "D") (pinfunction "D_D") (pintype "unspecified"))
    )
    (net (code "7") (name "Button") (class "Default")
      (node (ref "C4") (pin "1") (pinfunction "1_1") (pintype "input"))
      (node (ref "R5") (pin "2") (pinfunction "2_2") (pintype "input"))
      (node (ref "R6") (pin "1") (pinfunction "1_1") (pintype "input"))
      (node (ref "U11") (pin "7") (pinfunction "PB4_7") (pintype "unspecified"))
    )
    (net (code "8") (name "CPH") (class "Default")
      (node (ref "R10") (pin "2") (pinfunction "2_2") (pintype "input"))
      (node (ref "U9") (pin "5") (pinfunction "CP_H_5") (pintype "unspecified"))
    )
    (net (code "9") (name "CPL") (class "Default")
      (node (ref "R7") (pin "2") (pinfunction "2_2") (pintype "input"))
      (node (ref "U9") (pin "6") (pinfunction "CP_L_6") (pintype "unspecified"))
    )
    (net (code "10") (name "CS") (class "Default")
      (node (ref "R27") (pin "1") (pinfunction "1_1") (pintype "input"))
      (node (ref "U11") (pin "2") (pinfunction "PA4_2") (pintype "unspecified"))
      (node (ref "U18") (pin "14") (pinfunction "PC2_14") (pintype "unspecified"))
    )
    (net (code "11") (name "DCDC_FB") (class "Default")
      (node (ref "C13") (pin "2") (pinfunction "2_2") (pintype "input"))
      (node (ref "R12") (pin "2") (pinfunction "2_2") (pintype "input"))
      (node (ref "R9") (pin "1") (pinfunction "1_1") (pintype "input"))
      (node (ref "U9") (pin "18") (pinfunction "DCDC_FB_18") (pintype "unspecified"))
    )
    (net (code "12") (name "DCDC_LX") (class "Default")
      (node (ref "L1") (pin "1") (pinfunction "1_1") (pintype "unspecified"))
      (node (ref "U9") (pin "15") (pinfunction "DCDC_LX_15") (pintype "unspecified"))
    )
    (net (code "13") (name "DCDC_SS") (class "Default")
      (node (ref "C2") (pin "1") (pinfunction "1_1") (pintype "input"))
      (node (ref "U9") (pin "17") (pinfunction "DCDC_SS_17") (pintype "unspecified"))
    )
    (net (code "14") (name "GND") (class "Default")
      (node (ref "C1") (pin "1") (pinfunction "1_1") (pintype "input"))
      (node (ref "C10") (pin "2") (pinfunction "2_2") (pintype "input"))
      (node (ref "C11") (pin "1") (pinfunction "1_1") (pintype "input"))
      (node (ref "C12") (pin "2") (pinfunction "2_2") (pintype "unspecified"))
      (node (ref "C14") (pin "2") (pinfunction "2_2") (pintype "input"))
      (node (ref "C16") (pin "1") (pinfunction "1_1") (pintype "input"))
      (node (ref "C17") (pin "2") (pinfunction "2_2") (pintype "input"))
      (node (ref "C18") (pin "1") (pinfunction "1_1") (pintype "input"))
      (node (ref "C2") (pin "2") (pinfunction "2_2") (pintype "input"))
      (node (ref "C20") (pin "1") (pinfunction "1_1") (pintype "input"))
      (node (ref "C21") (pin "2") (pinfunction "2_2") (pintype "input"))
      (node (ref "C22") (pin "2") (pinfunction "2_2") (pintype "input"))
      (node (ref "C23") (pin "2") (pinfunction "2_2") (pintype "input"))
      (node (ref "C24") (pin "1") (pinfunction "1_1") (pintype "input"))
      (node (ref "C25") (pin "1") (pinfunction "1_1") (pintype "input"))
      (node (ref "C26") (pin "1") (pinfunction "1_1") (pintype "input"))
      (node (ref "C27") (pin "1") (pinfunction "1_1") (pintype "input"))
      (node (ref "C28") (pin "1") (pinfunction "1_1") (pintype "input"))
      (node (ref "C29") (pin "1") (pinfunction "1_1") (pintype "input"))
      (node (ref "C3") (pin "1") (pinfunction "1_1") (pintype "input"))
      (node (ref "C30") (pin "1") (pinfunction "1_1") (pintype "input"))
      (node (ref "C31") (pin "1") (pinfunction "1_1") (pintype "input"))
      (node (ref "C32") (pin "1") (pinfunction "1_1") (pintype "input"))
      (node (ref "C33") (pin "2") (pinfunction "2_2") (pintype "input"))
      (node (ref "C34") (pin "2") (pinfunction "2_2") (pintype "input"))
      (node (ref "C35") (pin "2") (pinfunction "2_2") (pintype "input"))
      (node (ref "C36") (pin "2") (pinfunction "2_2") (pintype "input"))
      (node (ref "C37") (pin "2") (pinfunction "2_2") (pintype "input"))
      (node (ref "C38") (pin "2") (pinfunction "2_2") (pintype "input"))
      (node (ref "C39") (pin "2") (pinfunction "2_2") (pintype "input"))
      (node (ref "C4") (pin "2") (pinfunction "2_2") (pintype "input"))
      (node (ref "C40") (pin "2") (pinfunction "2_2") (pintype "input"))
      (node (ref "C8") (pin "1") (pinfunction "1_1") (pintype "input"))
      (node (ref "C9") (pin "2") (pinfunction "2_2") (pintype "input"))
      (node (ref "CN1") (pin "5") (pinfunction "5_5") (pintype "unspecified"))
      (node (ref "CN1") (pin "6") (pinfunction "6_6") (pintype "unspecified"))
      (node (ref "CN2") (pin "5") (pinfunction "5_5") (pintype "unspecified"))
      (node (ref "CN2") (pin "6") (pinfunction "6_6") (pintype "unspecified"))
      (node (ref "D2") (pin "2") (pinfunction "A_2") (pintype "unspecified"))
      (node (ref "D3") (pin "2") (pinfunction "A_2") (pintype "unspecified"))
      (node (ref "D4") (pin "2") (pinfunction "A_2") (pintype "unspecified"))
      (node (ref "D5") (pin "2") (pinfunction "2_2") (pintype "unspecified"))
      (node (ref "D6") (pin "1") (pinfunction "1_1") (pintype "unspecified"))
      (node (ref "LCD1") (pin "1") (pinfunction "VSS_1") (pintype "unspecified"))
      (node (ref "LCD1") (pin "10") (pinfunction "DB3_10") (pintype "unspecified"))
      (node (ref "LCD1") (pin "7") (pinfunction "DB0_7") (pintype "unspecified"))
      (node (ref "LCD1") (pin "8") (pinfunction "DB1_8") (pintype "unspecified"))
      (node (ref "LCD1") (pin "9") (pinfunction "DB2_9") (pintype "unspecified"))
      (node (ref "LED1") (pin "2") (pinfunction "-_2") (pintype "unspecified"))
      (node (ref "LED10") (pin "2") (pinfunction "-_2") (pintype "unspecified"))
      (node (ref "LED11") (pin "2") (pinfunction "-_2") (pintype "unspecified"))
      (node (ref "LED12") (pin "2") (pinfunction "-_2") (pintype "unspecified"))
      (node (ref "LED13") (pin "2") (pinfunction "-_2") (pintype "unspecified"))
      (node (ref "LED14") (pin "2") (pinfunction "-_2") (pintype "unspecified"))
      (node (ref "LED15") (pin "2") (pinfunction "-_2") (pintype "unspecified"))
      (node (ref "LED2") (pin "2") (pinfunction "-_2") (pintype "unspecified"))
      (node (ref "LED3") (pin "2") (pinfunction "-_2") (pintype "unspecified"))
      (node (ref "LED4") (pin "2") (pinfunction "-_2") (pintype "unspecified"))
      (node (ref "LED5") (pin "2") (pinfunction "-_2") (pintype "unspecified"))
      (node (ref "LED6") (pin "2") (pinfunction "-_2") (pintype "unspecified"))
      (node (ref "LED7") (pin "2") (pinfunction "-_2") (pintype "unspecified"))
      (node (ref "LED8") (pin "2") (pinfunction "-_2") (pintype "unspecified"))
      (node (ref "LED9") (pin "2") (pinfunction "-_2") (pintype "unspecified"))
      (node (ref "Q1") (pin "2") (pinfunction "2_2") (pintype "input"))
      (node (ref "R1") (pin "1") (pinfunction "1_1") (pintype "input"))
      (node (ref "R12") (pin "1") (pinfunction "1_1") (pintype "input"))
      (node (ref "SW1") (pin "C") (pinfunction "C_C") (pintype "unspecified"))
      (node (ref "SW1") (pin "E") (pinfunction "E_E") (pintype "unspecified"))
      (node (ref "U1") (pin "2") (pinfunction "2_2") (pintype "unspecified"))
      (node (ref "U11") (pin "20") (pinfunction "GND_20") (pintype "unspecified"))
      (node (ref "U13") (pin "1") (pinfunction "1_1") (pintype "unspecified"))
      (node (ref "U14") (pin "1") (pinfunction "1_1") (pintype "unspecified"))
      (node (ref "U15") (pin "1") (pinfunction "1_1") (pintype "unspecified"))
      (node (ref "U16") (pin "1") (pinfunction "A1_1") (pintype "unspecified"))
      (node (ref "U16") (pin "2") (pinfunction "A0_2") (pintype "unspecified"))
      (node (ref "U16") (pin "6") (pinfunction "GND_6") (pintype "unspecified"))
      (node (ref "U17") (pin "1") (pinfunction "A0_1") (pintype "unspecified"))
      (node (ref "U17") (pin "2") (pinfunction "A1_2") (pintype "unspecified"))
      (node (ref "U17") (pin "3") (pinfunction "A2_3") (pintype "unspecified"))
      (node (ref "U17") (pin "8") (pinfunction "VSS_8") (pintype "unspecified"))
      (node (ref "U18") (pin "20") (pinfunction "GND_20") (pintype "unspecified"))
      (node (ref "U19") (pin "1") (pinfunction "1_1") (pintype "unspecified"))
      (node (ref "U20") (pin "1") (pinfunction "1_1") (pintype "unspecified"))
      (node (ref "U21") (pin "8") (pinfunction "VSS_8") (pintype "unspecified"))
      (node (ref "U22") (pin "1") (pinfunction "1_1") (pintype "unspecified"))
      (node (ref "U23") (pin "1") (pinfunction "1_1") (pintype "unspecified"))
      (node (ref "U24") (pin "10") (pinfunction "PGND2_10") (pintype "unspecified"))
      (node (ref "U24") (pin "18") (pinfunction "GND_18") (pintype "unspecified"))
      (node (ref "U24") (pin "3") (pinfunction "PGND1_3") (pintype "unspecified"))
      (node (ref "U24") (pin "4") (pinfunction "PGND1_4") (pintype "unspecified"))
      (node (ref "U24") (pin "9") (pinfunction "PGND2_9") (pintype "unspecified"))
      (node (ref "U25") (pin "10") (pinfunction "PGND2_10") (pintype "unspecified"))
      (node (ref "U25") (pin "18") (pinfunction "GND_18") (pintype "unspecified"))
      (node (ref "U25") (pin "3") (pinfunction "PGND1_3") (pintype "unspecified"))
      (node (ref "U25") (pin "4") (pinfunction "PGND1_4") (pintype "unspecified"))
      (node (ref "U25") (pin "9") (pinfunction "PGND2_9") (pintype "unspecified"))
      (node (ref "U26") (pin "10") (pinfunction "PGND2_10") (pintype "unspecified"))
      (node (ref "U26") (pin "18") (pinfunction "GND_18") (pintype "unspecified"))
      (node (ref "U26") (pin "3") (pinfunction "PGND1_3") (pintype "unspecified"))
      (node (ref "U26") (pin "4") (pinfunction "PGND1_4") (pintype "unspecified"))
      (node (ref "U26") (pin "9") (pinfunction "PGND2_9") (pintype "unspecified"))
      (node (ref "U27") (pin "10") (pinfunction "PGND2_10") (pintype "unspecified"))
      (node (ref "U27") (pin "18") (pinfunction "GND_18") (pintype "unspecified"))
      (node (ref "U27") (pin "3") (pinfunction "PGND1_3") (pintype "unspecified"))
      (node (ref "U27") (pin "4") (pinfunction "PGND1_4") (pintype "unspecified"))
      (node (ref "U27") (pin "9") (pinfunction "PGND2_9") (pintype "unspecified"))
      (node (ref "U28") (pin "1") (pinfunction "1_1") (pintype "unspecified"))
      (node (ref "U29") (pin "1") (pinfunction "1_1") (pintype "unspecified"))
      (node (ref "U4") (pin "2") (pinfunction "2_2") (pintype "unspecified"))
      (node (ref "U5") (pin "2") (pinfunction "2_2") (pintype "unspecified"))
      (node (ref "U6") (pin "2") (pinfunction "GND_2") (pintype "unspecified"))
      (node (ref "U7") (pin "13") (pinfunction "-V_13") (pintype "unspecified"))
      (node (ref "U8") (pin "2") (pinfunction "A_2") (pintype "unspecified"))
      (node (ref "U9") (pin "12") (pinfunction "KNX_B_12") (pintype "unspecified"))
      (node (ref "U9") (pin "16") (pinfunction "DCDC_GND_16") (pintype "unspecified"))
      (node (ref "U9") (pin "25") (pinfunction "EP_25") (pintype "unspecified"))
      (node (ref "U9") (pin "4") (pinfunction "KNX_B_4") (pintype "unspecified"))
    )
    (net (code "15") (name "IN_1") (class "Default")
      (node (ref "R20") (pin "2") (pinfunction "2_2") (pintype "input"))
      (node (ref "U11") (pin "5") (pinfunction "PA7_5") (pintype "unspecified"))
      (node (ref "U24") (pin "17") (pinfunction "BIN1_17") (pintype "unspecified"))
      (node (ref "U24") (pin "21") (pinfunction "AIN1_21") (pintype "unspecified"))
      (node (ref "U25") (pin "17") (pinfunction "BIN1_17") (pintype "unspecified"))
      (node (ref "U25") (pin "21") (pinfunction "AIN1_21") (pintype "unspecified"))
      (node (ref "U26") (pin "17") (pinfunction "BIN1_17") (pintype "unspecified"))
      (node (ref "U26") (pin "21") (pinfunction "AIN1_21") (pintype "unspecified"))
      (node (ref "U27") (pin "17") (pinfunction "BIN1_17") (pintype "unspecified"))
      (node (ref "U27") (pin "21") (pinfunction "AIN1_21") (pintype "unspecified"))
    )
    (net (code "16") (name "IN_2") (class "Default")
      (node (ref "R24") (pin "2") (pinfunction "2_2") (pintype "input"))
      (node (ref "U11") (pin "6") (pinfunction "PB5_6") (pintype "unspecified"))
      (node (ref "U24") (pin "16") (pinfunction "BIN2_16") (pintype "unspecified"))
      (node (ref "U24") (pin "22") (pinfunction "AIN2_22") (pintype "unspecified"))
      (node (ref "U25") (pin "16") (pinfunction "BIN2_16") (pintype "unspecified"))
      (node (ref "U25") (pin "22") (pinfunction "AIN2_22") (pintype "unspecified"))
      (node (ref "U26") (pin "16") (pinfunction "BIN2_16") (pintype "unspecified"))
      (node (ref "U26") (pin "22") (pinfunction "AIN2_22") (pintype "unspecified"))
      (node (ref "U27") (pin "16") (pinfunction "BIN2_16") (pintype "unspecified"))
      (node (ref "U27") (pin "22") (pinfunction "AIN2_22") (pintype "unspecified"))
    )
    (net (code "17") (name "KNC_AC") (class "Default")
      (node (ref "C5") (pin "2") (pinfunction "2_2") (pintype "input"))
      (node (ref "U8") (pin "1") (pinfunction "K_1") (pintype "unspecified"))
      (node (ref "U9") (pin "2") (pinfunction "KNX_AC_2") (pintype "unspecified"))
    )
    (net (code "18") (name "KNX+") (class "Default")
      (node (ref "C15") (pin "1") (pinfunction "1_1") (pintype "input"))
      (node (ref "D5") (pin "1") (pinfunction "1_1") (pintype "unspecified"))
      (node (ref "R1") (pin "2") (pinfunction "2_2") (pintype "input"))
      (node (ref "U3") (pin "2") (pinfunction "A_2") (pintype "unspecified"))
    )
    (net (code "19") (name "KNX_A") (class "Default")
      (node (ref "C5") (pin "1") (pinfunction "1_1") (pintype "input"))
      (node (ref "C7") (pin "1") (pinfunction "1_1") (pintype "input"))
      (node (ref "U12") (pin "2") (pinfunction "2_2") (pintype "unspecified"))
      (node (ref "U3") (pin "1") (pinfunction "K_1") (pintype "unspecified"))
      (node (ref "U4") (pin "1") (pinfunction "1_1") (pintype "unspecified"))
      (node (ref "U5") (pin "1") (pinfunction "1_1") (pintype "unspecified"))
      (node (ref "U9") (pin "11") (pinfunction "KNX_A_11") (pintype "unspecified"))
    )
    (net (code "20") (name "KNX_OK") (class "Default")
      (node (ref "U11") (pin "19") (pinfunction "PA3/EXTCLK_19") (pintype "unspecified"))
      (node (ref "U9") (pin "21") (pinfunction "KNX_OK_21") (pintype "unspecified"))
    )
    (net (code "21") (name "KNX_Rx") (class "Default")
      (node (ref "U11") (pin "18") (pinfunction "PA2_18") (pintype "unspecified"))
      (node (ref "U9") (pin "23") (pinfunction "KNX_RX_23") (pintype "unspecified"))
    )
    (net (code "22") (name "KNX_Tx") (class "Default")
      (node (ref "U11") (pin "17") (pinfunction "PA1_17") (pintype "unspecified"))
      (node (ref "U9") (pin "24") (pinfunction "KNX_TX_24") (pintype "unspecified"))
    )
    (net (code "23") (name "L") (class "Default")
      (node (ref "F1") (pin "2") (pinfunction "2_2") (pintype "unspecified"))
      (node (ref "U7") (pin "1") (pinfunction "AC/L_1") (pintype "unspecified"))
    )
    (net (code "24") (name "LED_1") (class "Default")
      (node (ref "R16") (pin "2") (pinfunction "2_2") (pintype "input"))
      (node (ref "U11") (pin "15") (pinfunction "PC3_15") (pintype "unspecified"))
    )
    (net (code "25") (name "LED_2") (class "Default")
      (node (ref "R29") (pin "2") (pinfunction "2_2") (pintype "input"))
      (node (ref "U18") (pin "15") (pinfunction "PC3_15") (pintype "unspecified"))
    )
    (net (code "26") (name "M1+") (class "Default")
      (node (ref "U27") (pin "1") (pinfunction "AO1_1") (pintype "unspecified"))
      (node (ref "U27") (pin "2") (pinfunction "AO1_2") (pintype "unspecified"))
      (node (ref "U36") (pin "1") (pinfunction "1_1") (pintype "unspecified"))
    )
    (net (code "27") (name "M1-") (class "Default")
      (node (ref "U27") (pin "5") (pinfunction "AO2_5") (pintype "unspecified"))
      (node (ref "U27") (pin "6") (pinfunction "AO2_6") (pintype "unspecified"))
      (node (ref "U36") (pin "2") (pinfunction "2_2") (pintype "unspecified"))
    )
    (net (code "28") (name "M1_EN") (class "Default")
      (node (ref "R34") (pin "2") (pinfunction "2_2") (pintype "input"))
      (node (ref "U17") (pin "4") (pinfunction "P0_4") (pintype "unspecified"))
      (node (ref "U27") (pin "23") (pinfunction "PWMA_23") (pintype "unspecified"))
    )
    (net (code "29") (name "M2+") (class "Default")
      (node (ref "U27") (pin "11") (pinfunction "BO1_11") (pintype "unspecified"))
      (node (ref "U27") (pin "12") (pinfunction "BO1_12") (pintype "unspecified"))
      (node (ref "U37") (pin "1") (pinfunction "1_1") (pintype "unspecified"))
    )
    (net (code "30") (name "M2-") (class "Default")
      (node (ref "U27") (pin "7") (pinfunction "BO2_7") (pintype "unspecified"))
      (node (ref "U27") (pin "8") (pinfunction "BO2_8") (pintype "unspecified"))
      (node (ref "U37") (pin "2") (pinfunction "2_2") (pintype "unspecified"))
    )
    (net (code "31") (name "M2_EN") (class "Default")
      (node (ref "R39") (pin "2") (pinfunction "2_2") (pintype "input"))
      (node (ref "U17") (pin "5") (pinfunction "P1_5") (pintype "unspecified"))
      (node (ref "U27") (pin "15") (pinfunction "PWMB_15") (pintype "unspecified"))
    )
    (net (code "32") (name "M3+") (class "Default")
      (node (ref "U26") (pin "1") (pinfunction "AO1_1") (pintype "unspecified"))
      (node (ref "U26") (pin "2") (pinfunction "AO1_2") (pintype "unspecified"))
      (node (ref "U34") (pin "1") (pinfunction "1_1") (pintype "unspecified"))
    )
    (net (code "33") (name "M3-") (class "Default")
      (node (ref "U26") (pin "5") (pinfunction "AO2_5") (pintype "unspecified"))
      (node (ref "U26") (pin "6") (pinfunction "AO2_6") (pintype "unspecified"))
      (node (ref "U34") (pin "2") (pinfunction "2_2") (pintype "unspecified"))
    )
    (net (code "34") (name "M3_EN") (class "Default")
      (node (ref "R33") (pin "2") (pinfunction "2_2") (pintype "input"))
      (node (ref "U17") (pin "6") (pinfunction "P2_6") (pintype "unspecified"))
      (node (ref "U26") (pin "23") (pinfunction "PWMA_23") (pintype "unspecified"))
    )
    (net (code "35") (name "M4+") (class "Default")
      (node (ref "U26") (pin "11") (pinfunction "BO1_11") (pintype "unspecified"))
      (node (ref "U26") (pin "12") (pinfunction "BO1_12") (pintype "unspecified"))
      (node (ref "U35") (pin "1") (pinfunction "1_1") (pintype "unspecified"))
    )
    (net (code "36") (name "M4-") (class "Default")
      (node (ref "U26") (pin "7") (pinfunction "BO2_7") (pintype "unspecified"))
      (node (ref "U26") (pin "8") (pinfunction "BO2_8") (pintype "unspecified"))
      (node (ref "U35") (pin "2") (pinfunction "2_2") (pintype "unspecified"))
    )
    (net (code "37") (name "M4_EN") (class "Default")
      (node (ref "R38") (pin "2") (pinfunction "2_2") (pintype "input"))
      (node (ref "U17") (pin "7") (pinfunction "P3_7") (pintype "unspecified"))
      (node (ref "U26") (pin "15") (pinfunction "PWMB_15") (pintype "unspecified"))
    )
    (net (code "38") (name "M5+") (class "Default")
      (node (ref "U24") (pin "1") (pinfunction "AO1_1") (pintype "unspecified"))
      (node (ref "U24") (pin "2") (pinfunction "AO1_2") (pintype "unspecified"))
      (node (ref "U30") (pin "1") (pinfunction "1_1") (pintype "unspecified"))
    )
    (net (code "39") (name "M5-") (class "Default")
      (node (ref "U24") (pin "5") (pinfunction "AO2_5") (pintype "unspecified"))
      (node (ref "U24") (pin "6") (pinfunction "AO2_6") (pintype "unspecified"))
      (node (ref "U30") (pin "2") (pinfunction "2_2") (pintype "unspecified"))
    )
    (net (code "40") (name "M5_EN") (class "Default")
      (node (ref "R31") (pin "2") (pinfunction "2_2") (pintype "input"))
      (node (ref "U17") (pin "9") (pinfunction "P4_9") (pintype "unspecified"))
      (node (ref "U24") (pin "23") (pinfunction "PWMA_23") (pintype "unspecified"))
    )
    (net (code "41") (name "M6+") (class "Default")
      (node (ref "U24") (pin "11") (pinfunction "BO1_11") (pintype "unspecified"))
      (node (ref "U24") (pin "12") (pinfunction "BO1_12") (pintype "unspecified"))
      (node (ref "U31") (pin "1") (pinfunction "1_1") (pintype "unspecified"))
    )
    (net (code "42") (name "M6-") (class "Default")
      (node (ref "U24") (pin "7") (pinfunction "BO2_7") (pintype "unspecified"))
      (node (ref "U24") (pin "8") (pinfunction "BO2_8") (pintype "unspecified"))
      (node (ref "U31") (pin "2") (pinfunction "2_2") (pintype "unspecified"))
    )
    (net (code "43") (name "M6_EN") (class "Default")
      (node (ref "R36") (pin "2") (pinfunction "2_2") (pintype "input"))
      (node (ref "U17") (pin "10") (pinfunction "P5_10") (pintype "unspecified"))
      (node (ref "U24") (pin "15") (pinfunction "PWMB_15") (pintype "unspecified"))
    )
    (net (code "44") (name "M7+") (class "Default")
      (node (ref "U25") (pin "1") (pinfunction "AO1_1") (pintype "unspecified"))
      (node (ref "U25") (pin "2") (pinfunction "AO1_2") (pintype "unspecified"))
      (node (ref "U32") (pin "1") (pinfunction "1_1") (pintype "unspecified"))
    )
    (net (code "45") (name "M7-") (class "Default")
      (node (ref "U25") (pin "5") (pinfunction "AO2_5") (pintype "unspecified"))
      (node (ref "U25") (pin "6") (pinfunction "AO2_6") (pintype "unspecified"))
      (node (ref "U32") (pin "2") (pinfunction "2_2") (pintype "unspecified"))
    )
    (net (code "46") (name "M7_EN") (class "Default")
      (node (ref "R32") (pin "2") (pinfunction "2_2") (pintype "input"))
      (node (ref "U17") (pin "11") (pinfunction "P6_11") (pintype "unspecified"))
      (node (ref "U25") (pin "23") (pinfunction "PWMA_23") (pintype "unspecified"))
    )
    (net (code "47") (name "M8+") (class "Default")
      (node (ref "U25") (pin "11") (pinfunction "BO1_11") (pintype "unspecified"))
      (node (ref "U25") (pin "12") (pinfunction "BO1_12") (pintype "unspecified"))
      (node (ref "U33") (pin "1") (pinfunction "1_1") (pintype "unspecified"))
    )
    (net (code "48") (name "M8-") (class "Default")
      (node (ref "U25") (pin "7") (pinfunction "BO2_7") (pintype "unspecified"))
      (node (ref "U25") (pin "8") (pinfunction "BO2_8") (pintype "unspecified"))
      (node (ref "U33") (pin "2") (pinfunction "2_2") (pintype "unspecified"))
    )
    (net (code "49") (name "M8_EN") (class "Default")
      (node (ref "R37") (pin "2") (pinfunction "2_2") (pintype "input"))
      (node (ref "U17") (pin "12") (pinfunction "P7_12") (pintype "unspecified"))
      (node (ref "U25") (pin "15") (pinfunction "PWMB_15") (pintype "unspecified"))
    )
    (net (code "50") (name "MISO") (class "Default")
      (node (ref "R21") (pin "1") (pinfunction "1_1") (pintype "input"))
      (node (ref "U11") (pin "13") (pinfunction "PC1_13") (pintype "unspecified"))
      (node (ref "U18") (pin "17") (pinfunction "PA1_17") (pintype "unspecified"))
    )
    (net (code "51") (name "MOSI") (class "Default")
      (node (ref "R25") (pin "1") (pinfunction "1_1") (pintype "input"))
      (node (ref "U11") (pin "14") (pinfunction "PC2_14") (pintype "unspecified"))
      (node (ref "U18") (pin "18") (pinfunction "PA2_18") (pintype "unspecified"))
    )
    (net (code "52") (name "M_VCC") (class "Default")
      (node (ref "C19") (pin "1") (pinfunction "1_1") (pintype "input"))
      (node (ref "C25") (pin "2") (pinfunction "2_2") (pintype "input"))
      (node (ref "C26") (pin "2") (pinfunction "2_2") (pintype "input"))
      (node (ref "C27") (pin "2") (pinfunction "2_2") (pintype "input"))
      (node (ref "C28") (pin "2") (pinfunction "2_2") (pintype "input"))
      (node (ref "C29") (pin "2") (pinfunction "2_2") (pintype "input"))
      (node (ref "C30") (pin "2") (pinfunction "2_2") (pintype "input"))
      (node (ref "C31") (pin "2") (pinfunction "2_2") (pintype "input"))
      (node (ref "C32") (pin "2") (pinfunction "2_2") (pintype "input"))
      (node (ref "R17") (pin "2") (pinfunction "2_2") (pintype "unspecified"))
      (node (ref "R23") (pin "2") (pinfunction "2_2") (pintype "input"))
      (node (ref "U24") (pin "13") (pinfunction "VM2_13") (pintype "unspecified"))
      (node (ref "U24") (pin "14") (pinfunction "VM3_14") (pintype "unspecified"))
      (node (ref "U24") (pin "24") (pinfunction "VM1_24") (pintype "unspecified"))
      (node (ref "U25") (pin "13") (pinfunction "VM2_13") (pintype "unspecified"))
      (node (ref "U25") (pin "14") (pinfunction "VM3_14") (pintype "unspecified"))
      (node (ref "U25") (pin "24") (pinfunction "VM1_24") (pintype "unspecified"))
      (node (ref "U26") (pin "13") (pinfunction "VM2_13") (pintype "unspecified"))
      (node (ref "U26") (pin "14") (pinfunction "VM3_14") (pintype "unspecified"))
      (node (ref "U26") (pin "24") (pinfunction "VM1_24") (pintype "unspecified"))
      (node (ref "U27") (pin "13") (pinfunction "VM2_13") (pintype "unspecified"))
      (node (ref "U27") (pin "14") (pinfunction "VM3_14") (pintype "unspecified"))
      (node (ref "U27") (pin "24") (pinfunction "VM1_24") (pintype "unspecified"))
    )
    (net (code "53") (name "N") (class "Default")
      (node (ref "U2") (pin "3") (pinfunction "3_3") (pintype "unspecified"))
      (node (ref "U7") (pin "24") (pinfunction "AC/N_24") (pintype "unspecified"))
    )
    (net (code "54") (name "Net-(C11-Pad2)") (class "Default")
      (node (ref "C11") (pin "2") (pinfunction "2_2") (pintype "input"))
      (node (ref "R7") (pin "1") (pinfunction "1_1") (pintype "input"))
    )
    (net (code "55") (name "Net-(C15-Pad2)") (class "Default")
      (node (ref "C15") (pin "2") (pinfunction "2_2") (pintype "input"))
      (node (ref "R10") (pin "1") (pinfunction "1_1") (pintype "input"))
    )
    (net (code "56") (name "Net-(D1-K)") (class "Default")
      (node (ref "D1") (pin "1") (pinfunction "K_1") (pintype "unspecified"))
      (node (ref "U6") (pin "1") (pinfunction "+Vin_1") (pintype "unspecified"))
    )
    (net (code "57") (name "Net-(F1-Pad1)") (class "Default")
      (node (ref "F1") (pin "1") (pinfunction "1_1") (pintype "unspecified"))
      (node (ref "U2") (pin "1") (pinfunction "1_1") (pintype "unspecified"))
    )
    (net (code "58") (name "Net-(LCD1-BLK)") (class "Default")
      (node (ref "LCD1") (pin "16") (pinfunction "BLK_16") (pintype "unspecified"))
      (node (ref "Q1") (pin "3") (pinfunction "3_3") (pintype "input"))
    )
    (net (code "59") (name "Net-(LCD1-DB4)") (class "Default")
      (node (ref "LCD1") (pin "11") (pinfunction "DB4_11") (pintype "unspecified"))
      (node (ref "U21") (pin "9") (pinfunction "P4_9") (pintype "unspecified"))
    )
    (net (code "60") (name "Net-(LCD1-DB5)") (class "Default")
      (node (ref "LCD1") (pin "12") (pinfunction "DB5_12") (pintype "unspecified"))
      (node (ref "U21") (pin "10") (pinfunction "P5_10") (pintype "unspecified"))
    )
    (net (code "61") (name "Net-(LCD1-DB6)") (class "Default")
      (node (ref "LCD1") (pin "13") (pinfunction "DB6_13") (pintype "unspecified"))
      (node (ref "U21") (pin "11") (pinfunction "P6_11") (pintype "unspecified"))
    )
    (net (code "62") (name "Net-(LCD1-DB7)") (class "Default")
      (node (ref "LCD1") (pin "14") (pinfunction "DB7_14") (pintype "unspecified"))
      (node (ref "U21") (pin "12") (pinfunction "P7_12") (pintype "unspecified"))
    )
    (net (code "63") (name "Net-(LCD1-E)") (class "Default")
      (node (ref "LCD1") (pin "6") (pinfunction "E_6") (pintype "unspecified"))
      (node (ref "U21") (pin "6") (pinfunction "P2_6") (pintype "unspecified"))
    )
    (net (code "64") (name "Net-(LCD1-RS)") (class "Default")
      (node (ref "LCD1") (pin "4") (pinfunction "RS_4") (pintype "unspecified"))
      (node (ref "U21") (pin "4") (pinfunction "P0_4") (pintype "unspecified"))
    )
    (net (code "65") (name "Net-(LCD1-RW)") (class "Default")
      (node (ref "LCD1") (pin "5") (pinfunction "RW_5") (pintype "unspecified"))
      (node (ref "U21") (pin "5") (pinfunction "P1_5") (pintype "unspecified"))
    )
    (net (code "66") (name "Net-(LCD1-V0)") (class "Default")
      (node (ref "D6") (pin "2") (pinfunction "2_2") (pintype "unspecified"))
      (node (ref "LCD1") (pin "3") (pinfunction "V0_3") (pintype "unspecified"))
    )
    (net (code "67") (name "Net-(LED1-+)") (class "Default")
      (node (ref "LED1") (pin "1") (pinfunction "+_1") (pintype "unspecified"))
      (node (ref "R2") (pin "1") (pinfunction "1_1") (pintype "input"))
    )
    (net (code "68") (name "Net-(LED2-+)") (class "Default")
      (node (ref "LED2") (pin "1") (pinfunction "+_1") (pintype "unspecified"))
      (node (ref "R3") (pin "1") (pinfunction "1_1") (pintype "input"))
    )
    (net (code "69") (name "Net-(LED3-+)") (class "Default")
      (node (ref "LED3") (pin "1") (pinfunction "+_1") (pintype "unspecified"))
      (node (ref "R4") (pin "1") (pinfunction "1_1") (pintype "input"))
    )
    (net (code "70") (name "Net-(LED4-+)") (class "Default")
      (node (ref "LED4") (pin "1") (pinfunction "+_1") (pintype "unspecified"))
      (node (ref "R16") (pin "1") (pinfunction "1_1") (pintype "input"))
    )
    (net (code "71") (name "Net-(LED5-+)") (class "Default")
      (node (ref "LED5") (pin "1") (pinfunction "+_1") (pintype "unspecified"))
      (node (ref "R20") (pin "1") (pinfunction "1_1") (pintype "input"))
    )
    (net (code "72") (name "Net-(LED6-+)") (class "Default")
      (node (ref "LED6") (pin "1") (pinfunction "+_1") (pintype "unspecified"))
      (node (ref "R24") (pin "1") (pinfunction "1_1") (pintype "input"))
    )
    (net (code "73") (name "Net-(LED7-+)") (class "Default")
      (node (ref "LED7") (pin "1") (pinfunction "+_1") (pintype "unspecified"))
      (node (ref "R29") (pin "1") (pinfunction "1_1") (pintype "input"))
    )
    (net (code "74") (name "Net-(LED8-+)") (class "Default")
      (node (ref "LED8") (pin "1") (pinfunction "+_1") (pintype "unspecified"))
      (node (ref "R31") (pin "1") (pinfunction "1_1") (pintype "input"))
    )
    (net (code "75") (name "Net-(LED9-+)") (class "Default")
      (node (ref "LED9") (pin "1") (pinfunction "+_1") (pintype "unspecified"))
      (node (ref "R32") (pin "1") (pinfunction "1_1") (pintype "input"))
    )
    (net (code "76") (name "Net-(LED10-+)") (class "Default")
      (node (ref "LED10") (pin "1") (pinfunction "+_1") (pintype "unspecified"))
      (node (ref "R33") (pin "1") (pinfunction "1_1") (pintype "input"))
    )
    (net (code "77") (name "Net-(LED11-+)") (class "Default")
      (node (ref "LED11") (pin "1") (pinfunction "+_1") (pintype "unspecified"))
      (node (ref "R34") (pin "1") (pinfunction "1_1") (pintype "input"))
    )
    (net (code "78") (name "Net-(LED12-+)") (class "Default")
      (node (ref "LED12") (pin "1") (pinfunction "+_1") (pintype "unspecified"))
      (node (ref "R36") (pin "1") (pinfunction "1_1") (pintype "input"))
    )
    (net (code "79") (name "Net-(LED13-+)") (class "Default")
      (node (ref "LED13") (pin "1") (pinfunction "+_1") (pintype "unspecified"))
      (node (ref "R37") (pin "1") (pinfunction "1_1") (pintype "input"))
    )
    (net (code "80") (name "Net-(LED14-+)") (class "Default")
      (node (ref "LED14") (pin "1") (pinfunction "+_1") (pintype "unspecified"))
      (node (ref "R38") (pin "1") (pinfunction "1_1") (pintype "input"))
    )
    (net (code "81") (name "Net-(LED15-+)") (class "Default")
      (node (ref "LED15") (pin "1") (pinfunction "+_1") (pintype "unspecified"))
      (node (ref "R39") (pin "1") (pinfunction "1_1") (pintype "input"))
    )
    (net (code "82") (name "Net-(U9-VREF)") (class "Default")
      (node (ref "C3") (pin "2") (pinfunction "2_2") (pintype "input"))
      (node (ref "U9") (pin "8") (pinfunction "VREF_8") (pintype "unspecified"))
    )
    (net (code "83") (name "Net-(U16-IN+)") (class "Default")
      (node (ref "R22") (pin "1") (pinfunction "1_1") (pintype "input"))
      (node (ref "U16") (pin "8") (pinfunction "IN+_8") (pintype "unspecified"))
    )
    (net (code "84") (name "Net-(U16-IN-)") (class "Default")
      (node (ref "R23") (pin "1") (pinfunction "1_1") (pintype "input"))
      (node (ref "U16") (pin "7") (pinfunction "IN-_7") (pintype "unspecified"))
    )
    (net (code "85") (name "Net-(U21-P3)") (class "Default")
      (node (ref "Q1") (pin "1") (pinfunction "1_1") (pintype "input"))
      (node (ref "R40") (pin "1") (pinfunction "1_1") (pintype "input"))
      (node (ref "U21") (pin "7") (pinfunction "P3_7") (pintype "unspecified"))
    )
    (net (code "86") (name "PE") (class "Default")
      (node (ref "U2") (pin "2") (pinfunction "2_2") (pintype "unspecified"))
    )
    (net (code "87") (name "R68") (class "Default")
      (node (ref "U12") (pin "1") (pinfunction "1_1") (pintype "unspecified"))
      (node (ref "U9") (pin "3") (pinfunction "R68_3") (pintype "unspecified"))
    )
    (net (code "88") (name "RxD_1") (class "Default")
      (node (ref "CN1") (pin "2") (pinfunction "2_2") (pintype "unspecified"))
      (node (ref "U11") (pin "8") (pinfunction "TOSC1/PB3_8") (pintype "unspecified"))
    )
    (net (code "89") (name "RxD_2") (class "Default")
      (node (ref "CN2") (pin "2") (pinfunction "2_2") (pintype "unspecified"))
      (node (ref "U18") (pin "8") (pinfunction "TOSC1/PB3_8") (pintype "unspecified"))
    )
    (net (code "90") (name "SCK") (class "Default")
      (node (ref "R18") (pin "1") (pinfunction "1_1") (pintype "input"))
      (node (ref "U11") (pin "12") (pinfunction "PC0_12") (pintype "unspecified"))
      (node (ref "U18") (pin "19") (pinfunction "PA3/EXTCLK_19") (pintype "unspecified"))
    )
    (net (code "91") (name "SCL") (class "Default")
      (node (ref "R15") (pin "1") (pinfunction "1_1") (pintype "input"))
      (node (ref "U11") (pin "11") (pinfunction "PB0_11") (pintype "unspecified"))
      (node (ref "U16") (pin "4") (pinfunction "SCL_4") (pintype "unspecified"))
      (node (ref "U17") (pin "14") (pinfunction "SCL_14") (pintype "unspecified"))
      (node (ref "U21") (pin "14") (pinfunction "SCL_14") (pintype "unspecified"))
    )
    (net (code "92") (name "SDA") (class "Default")
      (node (ref "R14") (pin "1") (pinfunction "1_1") (pintype "input"))
      (node (ref "U11") (pin "10") (pinfunction "PB1_10") (pintype "unspecified"))
      (node (ref "U16") (pin "3") (pinfunction "SDA_3") (pintype "unspecified"))
      (node (ref "U17") (pin "15") (pinfunction "SDA_15") (pintype "unspecified"))
      (node (ref "U21") (pin "15") (pinfunction "SDA_15") (pintype "unspecified"))
    )
    (net (code "93") (name "T0") (class "Default")
      (node (ref "R13") (pin "2") (pinfunction "2_2") (pintype "input"))
      (node (ref "U13") (pin "2") (pinfunction "2_2") (pintype "unspecified"))
      (node (ref "U18") (pin "2") (pinfunction "PA4_2") (pintype "unspecified"))
    )
    (net (code "94") (name "T1") (class "Default")
      (node (ref "R19") (pin "2") (pinfunction "2_2") (pintype "input"))
      (node (ref "U14") (pin "2") (pinfunction "2_2") (pintype "unspecified"))
      (node (ref "U18") (pin "3") (pinfunction "PA5_3") (pintype "unspecified"))
    )
    (net (code "95") (name "T2") (class "Default")
      (node (ref "R26") (pin "2") (pinfunction "2_2") (pintype "input"))
      (node (ref "U15") (pin "2") (pinfunction "2_2") (pintype "unspecified"))
      (node (ref "U18") (pin "4") (pinfunction "PA6_4") (pintype "unspecified"))
    )
    (net (code "96") (name "T3") (class "Default")
      (node (ref "R28") (pin "2") (pinfunction "2_2") (pintype "input"))
      (node (ref "U18") (pin "5") (pinfunction "PA7_5") (pintype "unspecified"))
      (node (ref "U19") (pin "2") (pinfunction "2_2") (pintype "unspecified"))
    )
    (net (code "97") (name "T4") (class "Default")
      (node (ref "R30") (pin "2") (pinfunction "2_2") (pintype "input"))
      (node (ref "U18") (pin "6") (pinfunction "PB5_6") (pintype "unspecified"))
      (node (ref "U20") (pin "2") (pinfunction "2_2") (pintype "unspecified"))
    )
    (net (code "98") (name "T5") (class "Default")
      (node (ref "R35") (pin "2") (pinfunction "2_2") (pintype "input"))
      (node (ref "U18") (pin "7") (pinfunction "PB4_7") (pintype "unspecified"))
      (node (ref "U22") (pin "2") (pinfunction "2_2") (pintype "unspecified"))
    )
    (net (code "99") (name "T6") (class "Default")
      (node (ref "R41") (pin "2") (pinfunction "2_2") (pintype "input"))
      (node (ref "U18") (pin "10") (pinfunction "PB1_10") (pintype "unspecified"))
      (node (ref "U23") (pin "2") (pinfunction "2_2") (pintype "unspecified"))
    )
    (net (code "100") (name "T7") (class "Default")
      (node (ref "R42") (pin "2") (pinfunction "2_2") (pintype "input"))
      (node (ref "U18") (pin "13") (pinfunction "PC1_13") (pintype "unspecified"))
      (node (ref "U28") (pin "2") (pinfunction "2_2") (pintype "unspecified"))
    )
    (net (code "101") (name "T8") (class "Default")
      (node (ref "R43") (pin "2") (pinfunction "2_2") (pintype "input"))
      (node (ref "U18") (pin "12") (pinfunction "PC0_12") (pintype "unspecified"))
      (node (ref "U29") (pin "2") (pinfunction "2_2") (pintype "unspecified"))
    )
    (net (code "102") (name "TxD_1") (class "Default")
      (node (ref "CN1") (pin "4") (pinfunction "4_4") (pintype "unspecified"))
      (node (ref "U11") (pin "9") (pinfunction "TOSC2/PB2_9") (pintype "unspecified"))
    )
    (net (code "103") (name "TxD_2") (class "Default")
      (node (ref "CN2") (pin "4") (pinfunction "4_4") (pintype "unspecified"))
      (node (ref "U18") (pin "9") (pinfunction "TOSC2/PB2_9") (pintype "unspecified"))
    )
    (net (code "104") (name "UPDI_1") (class "Default")
      (node (ref "CN1") (pin "3") (pinfunction "3_3") (pintype "unspecified"))
      (node (ref "U11") (pin "16") (pinfunction "PA0/RESET#/UPDI_16") (pintype "unspecified"))
    )
    (net (code "105") (name "UPDI_2") (class "Default")
      (node (ref "CN2") (pin "3") (pinfunction "3_3") (pintype "unspecified"))
      (node (ref "U18") (pin "16") (pinfunction "PA0/RESET#/UPDI_16") (pintype "unspecified"))
    )
    (net (code "106") (name "VCC") (class "Default")
      (node (ref "C1") (pin "2") (pinfunction "2_2") (pintype "input"))
      (node (ref "U9") (pin "20") (pinfunction "VCCCORE_20") (pintype "unspecified"))
      (node (ref "U9") (pin "22") (pinfunction "VCC_SEL_22") (pintype "unspecified"))
    )
    (net (code "107") (name "VCC_OK") (class "Default")
      (node (ref "R4") (pin "2") (pinfunction "2_2") (pintype "input"))
      (node (ref "U9") (pin "19") (pinfunction "VCC_OK_19") (pintype "unspecified"))
    )
    (net (code "108") (name "VDDHV") (class "Default")
      (node (ref "C12") (pin "1") (pinfunction "1_1") (pintype "unspecified"))
      (node (ref "C14") (pin "1") (pinfunction "1_1") (pintype "input"))
      (node (ref "C6") (pin "1") (pinfunction "1_1") (pintype "input"))
      (node (ref "U10") (pin "1") (pinfunction "K_1") (pintype "unspecified"))
      (node (ref "U9") (pin "14") (pinfunction "DCDC_IN_14") (pintype "unspecified"))
      (node (ref "U9") (pin "9") (pinfunction "VDDHV_9") (pintype "unspecified"))
    )
    (net (code "109") (name "VDDHV_PD") (class "Default")
      (node (ref "U10") (pin "2") (pinfunction "A_2") (pintype "unspecified"))
      (node (ref "U9") (pin "10") (pinfunction "VDDHV_PD_10") (pintype "unspecified"))
    )
    (net (code "110") (name "VFLT") (class "Default")
      (node (ref "C6") (pin "2") (pinfunction "2_2") (pintype "input"))
      (node (ref "C8") (pin "2") (pinfunction "2_2") (pintype "input"))
      (node (ref "U9") (pin "7") (pinfunction "VFLT_7") (pintype "unspecified"))
    )
    (net (code "111") (name "VGATE") (class "Default")
      (node (ref "C7") (pin "2") (pinfunction "2_2") (pintype "input"))
      (node (ref "U9") (pin "13") (pinfunction "VGATE_13") (pintype "unspecified"))
    )
    (net (code "112") (name "VOUT") (class "Default")
      (node (ref "C13") (pin "1") (pinfunction "1_1") (pintype "input"))
      (node (ref "C17") (pin "1") (pinfunction "1_1") (pintype "input"))
      (node (ref "L1") (pin "2") (pinfunction "2_2") (pintype "unspecified"))
      (node (ref "R9") (pin "2") (pinfunction "2_2") (pintype "input"))
    )
    (net (code "113") (name "unconnected-(D6-Pad3)") (class "Default")
      (node (ref "D6") (pin "3") (pinfunction "3_3") (pintype "unspecified+no_connect"))
    )
    (net (code "114") (name "unconnected-(SW1-EH-Pad6)") (class "Default")
      (node (ref "SW1") (pin "6") (pinfunction "EH_6") (pintype "unspecified+no_connect"))
    )
    (net (code "115") (name "unconnected-(SW1-EH-Pad7)") (class "Default")
      (node (ref "SW1") (pin "7") (pinfunction "EH_7") (pintype "unspecified+no_connect"))
    )
    (net (code "116") (name "unconnected-(U9-VDD_REGIN-Pad1)") (class "Default")
      (node (ref "U9") (pin "1") (pinfunction "VDD_REGIN_1") (pintype "unspecified"))
    )
    (net (code "117") (name "unconnected-(U17-INT#-Pad13)") (class "Default")
      (node (ref "U17") (pin "13") (pinfunction "INT#_13") (pintype "unspecified+no_connect"))
    )
    (net (code "118") (name "unconnected-(U18-PB0-Pad11)") (class "Default")
      (node (ref "U18") (pin "11") (pinfunction "PB0_11") (pintype "unspecified+no_connect"))
    )
    (net (code "119") (name "unconnected-(U21-INT#-Pad13)") (class "Default")
      (node (ref "U21") (pin "13") (pinfunction "INT#_13") (pintype "unspecified+no_connect"))
    )
  )
)
